# FY.net
KiCad netlist of a schematic drawn in EAGLE
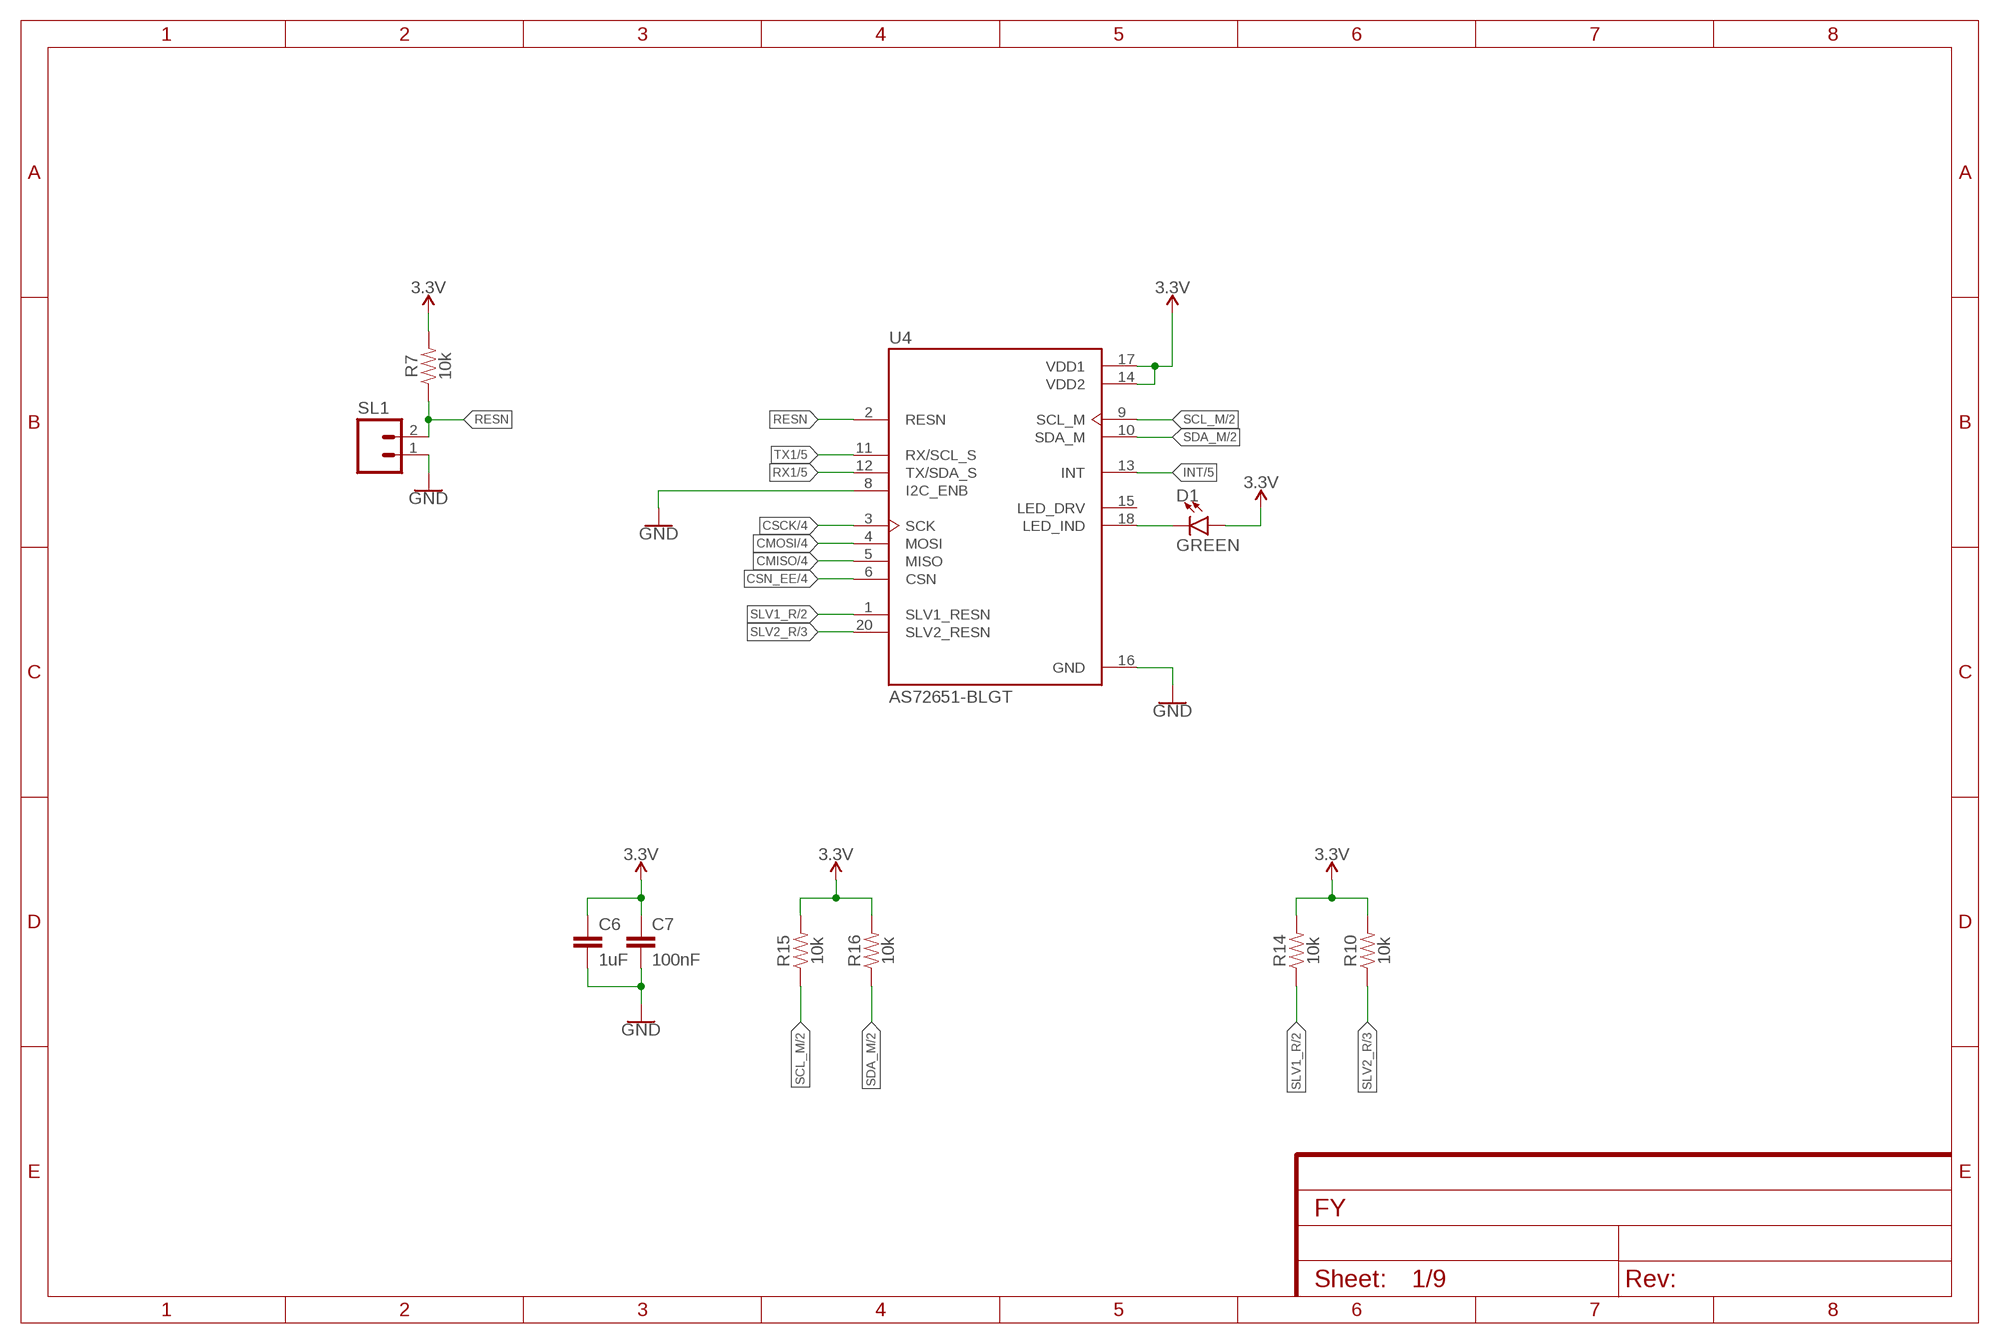
[diagram p0: schematic, sheet 1]
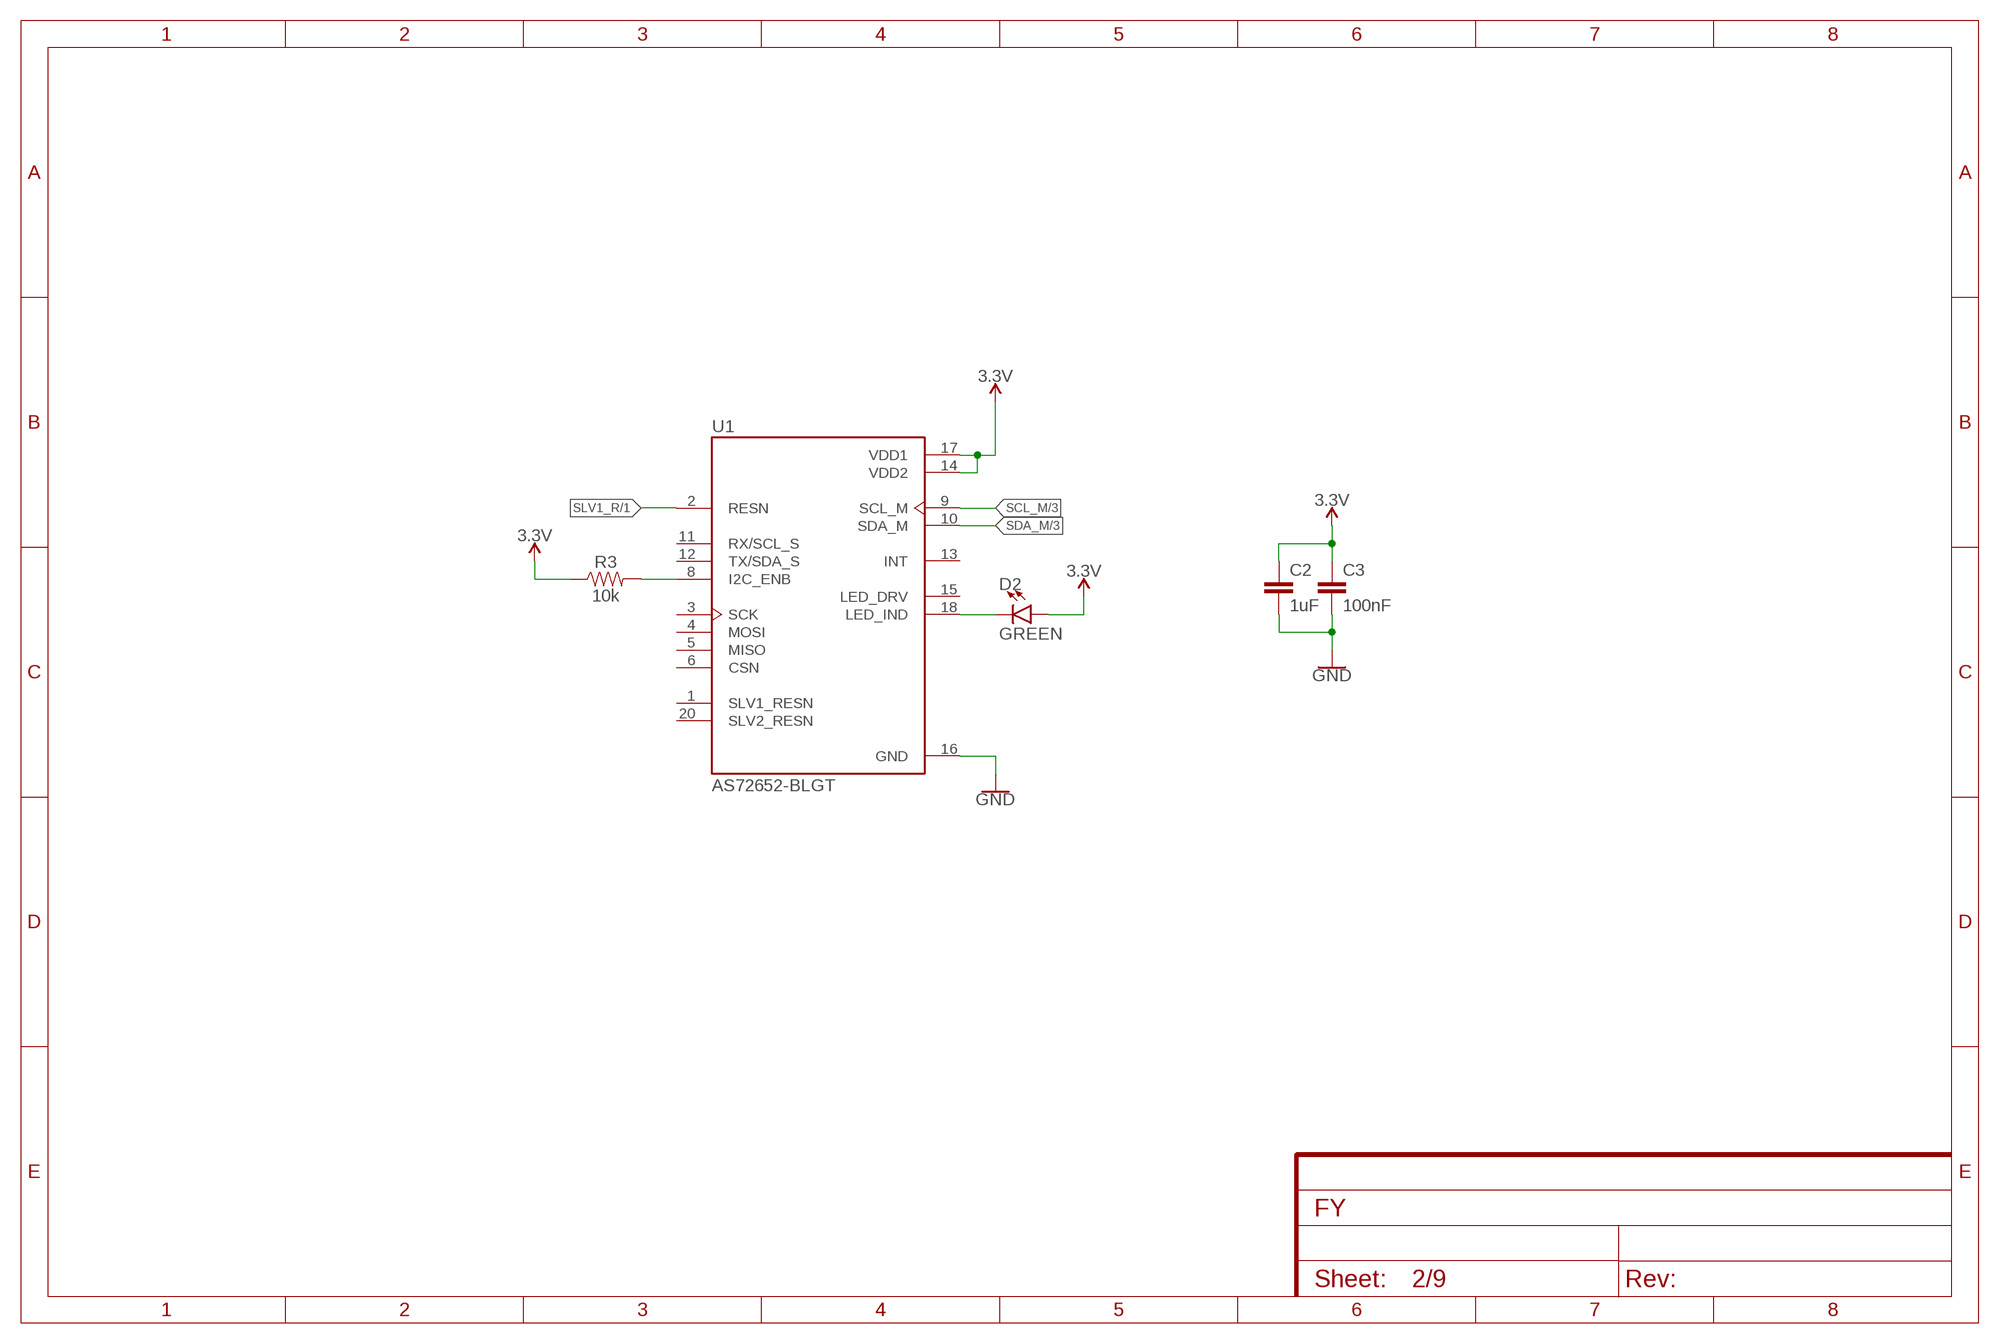
[diagram p1: schematic, sheet 2]
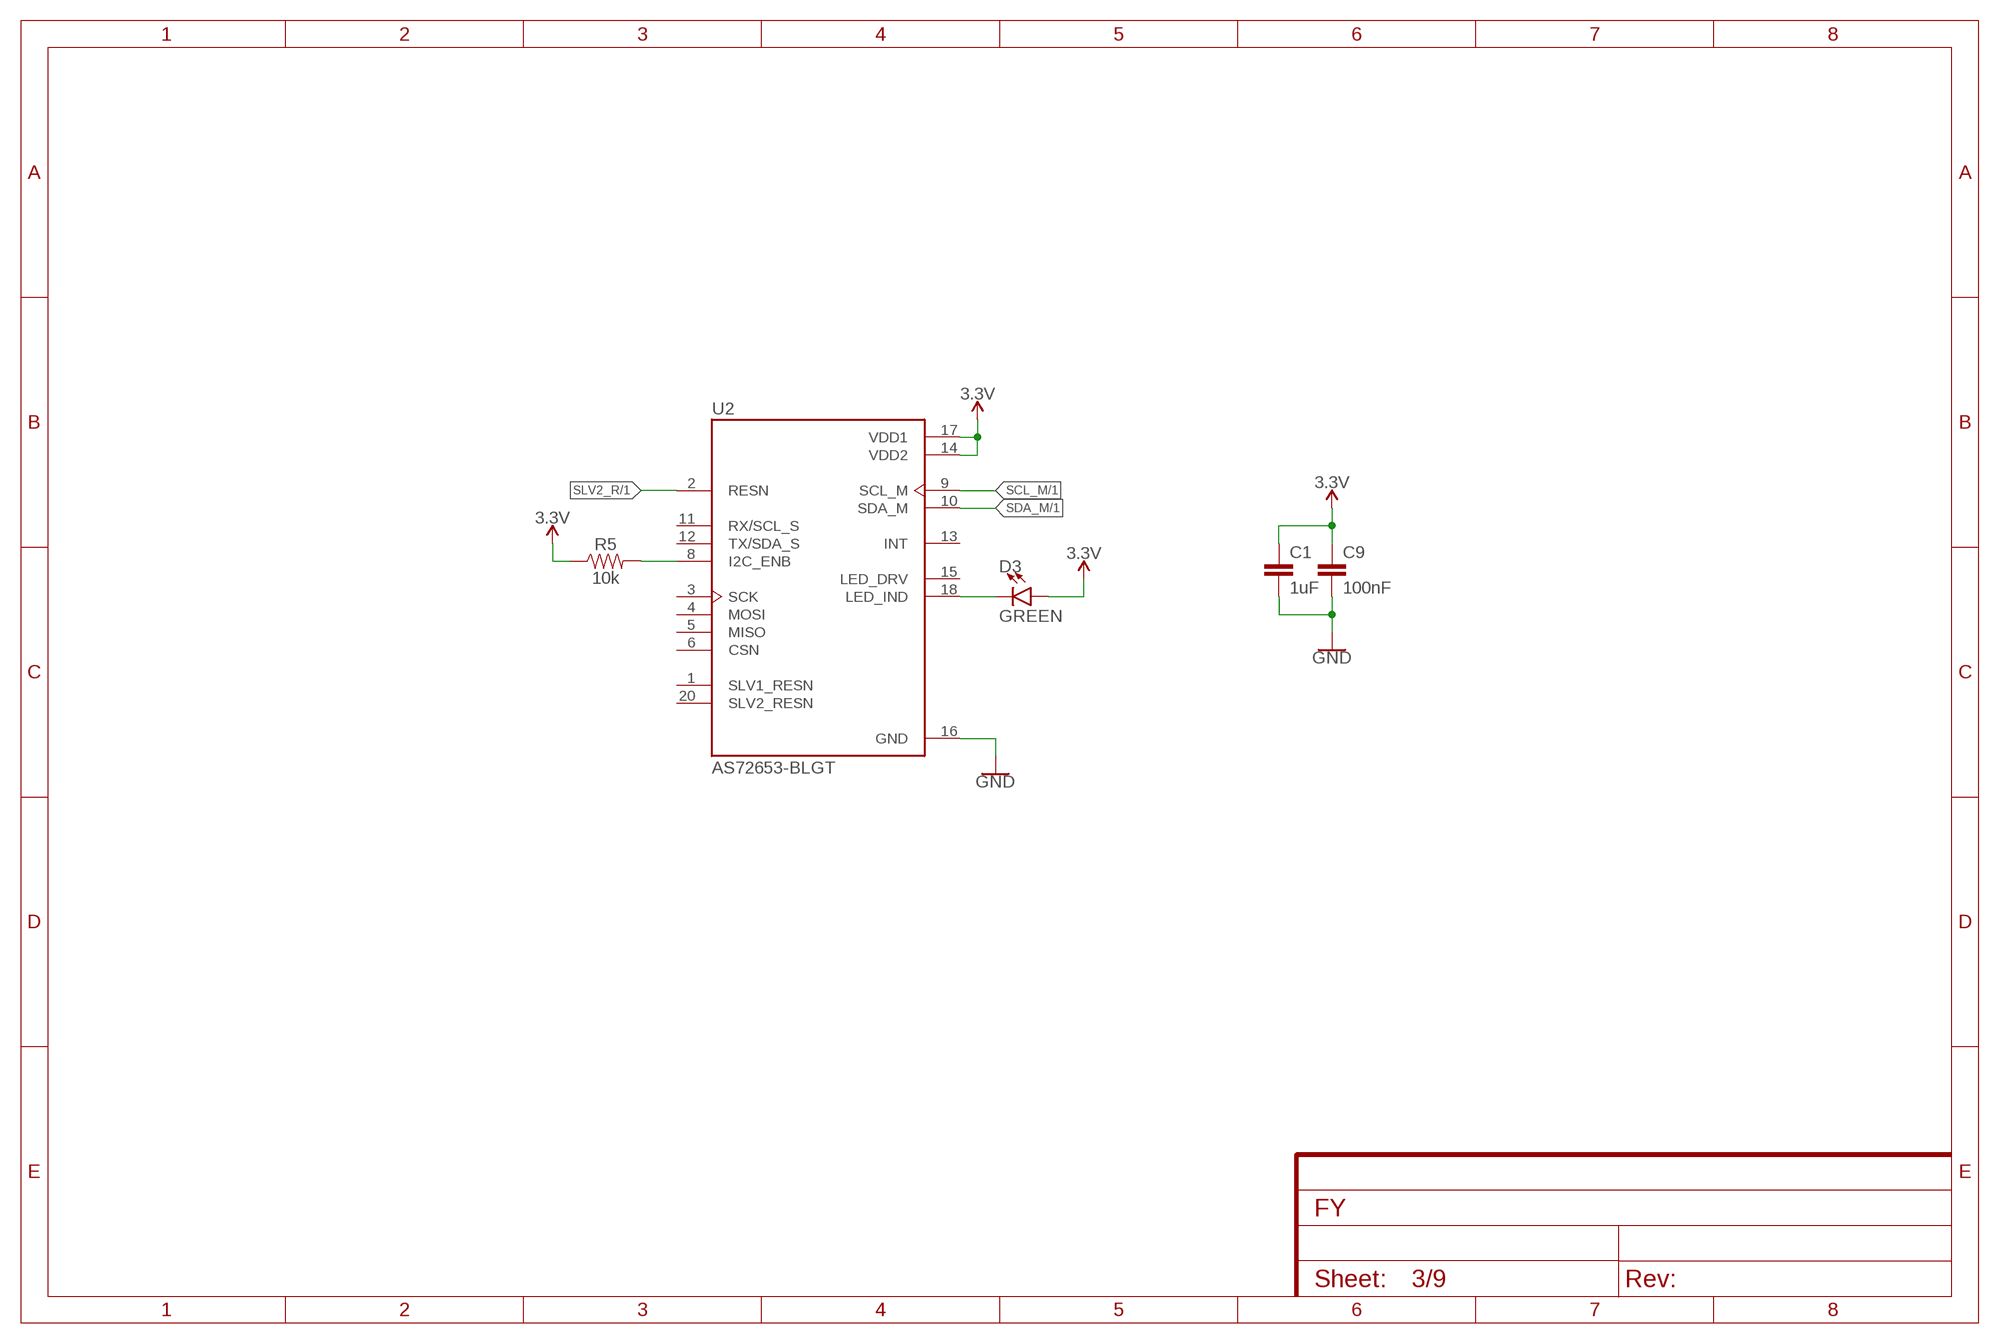
[diagram p2: schematic, sheet 3]
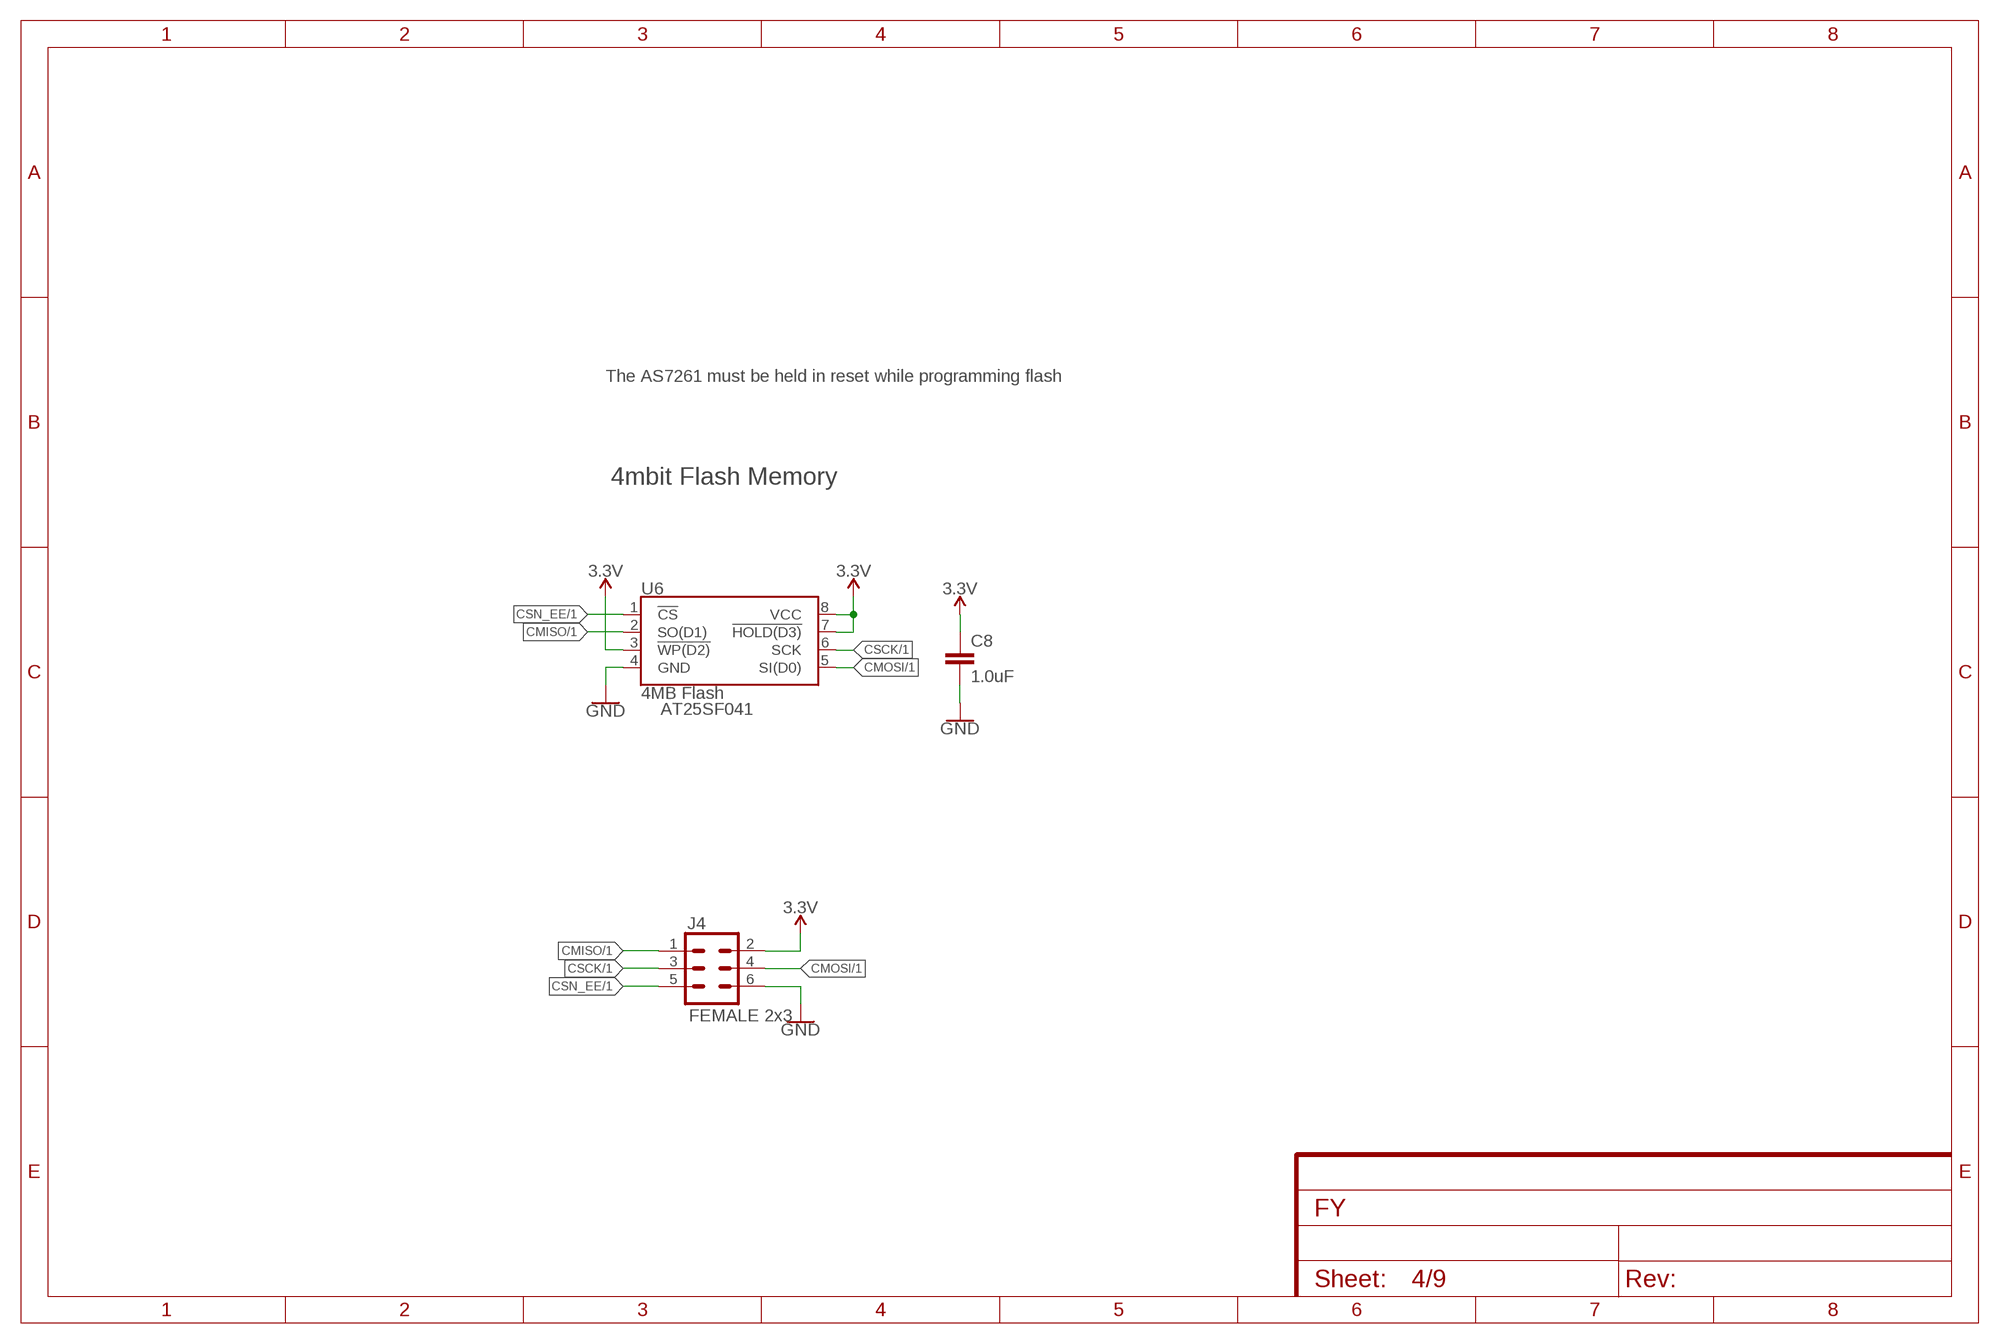
[diagram p3: schematic, sheet 4]
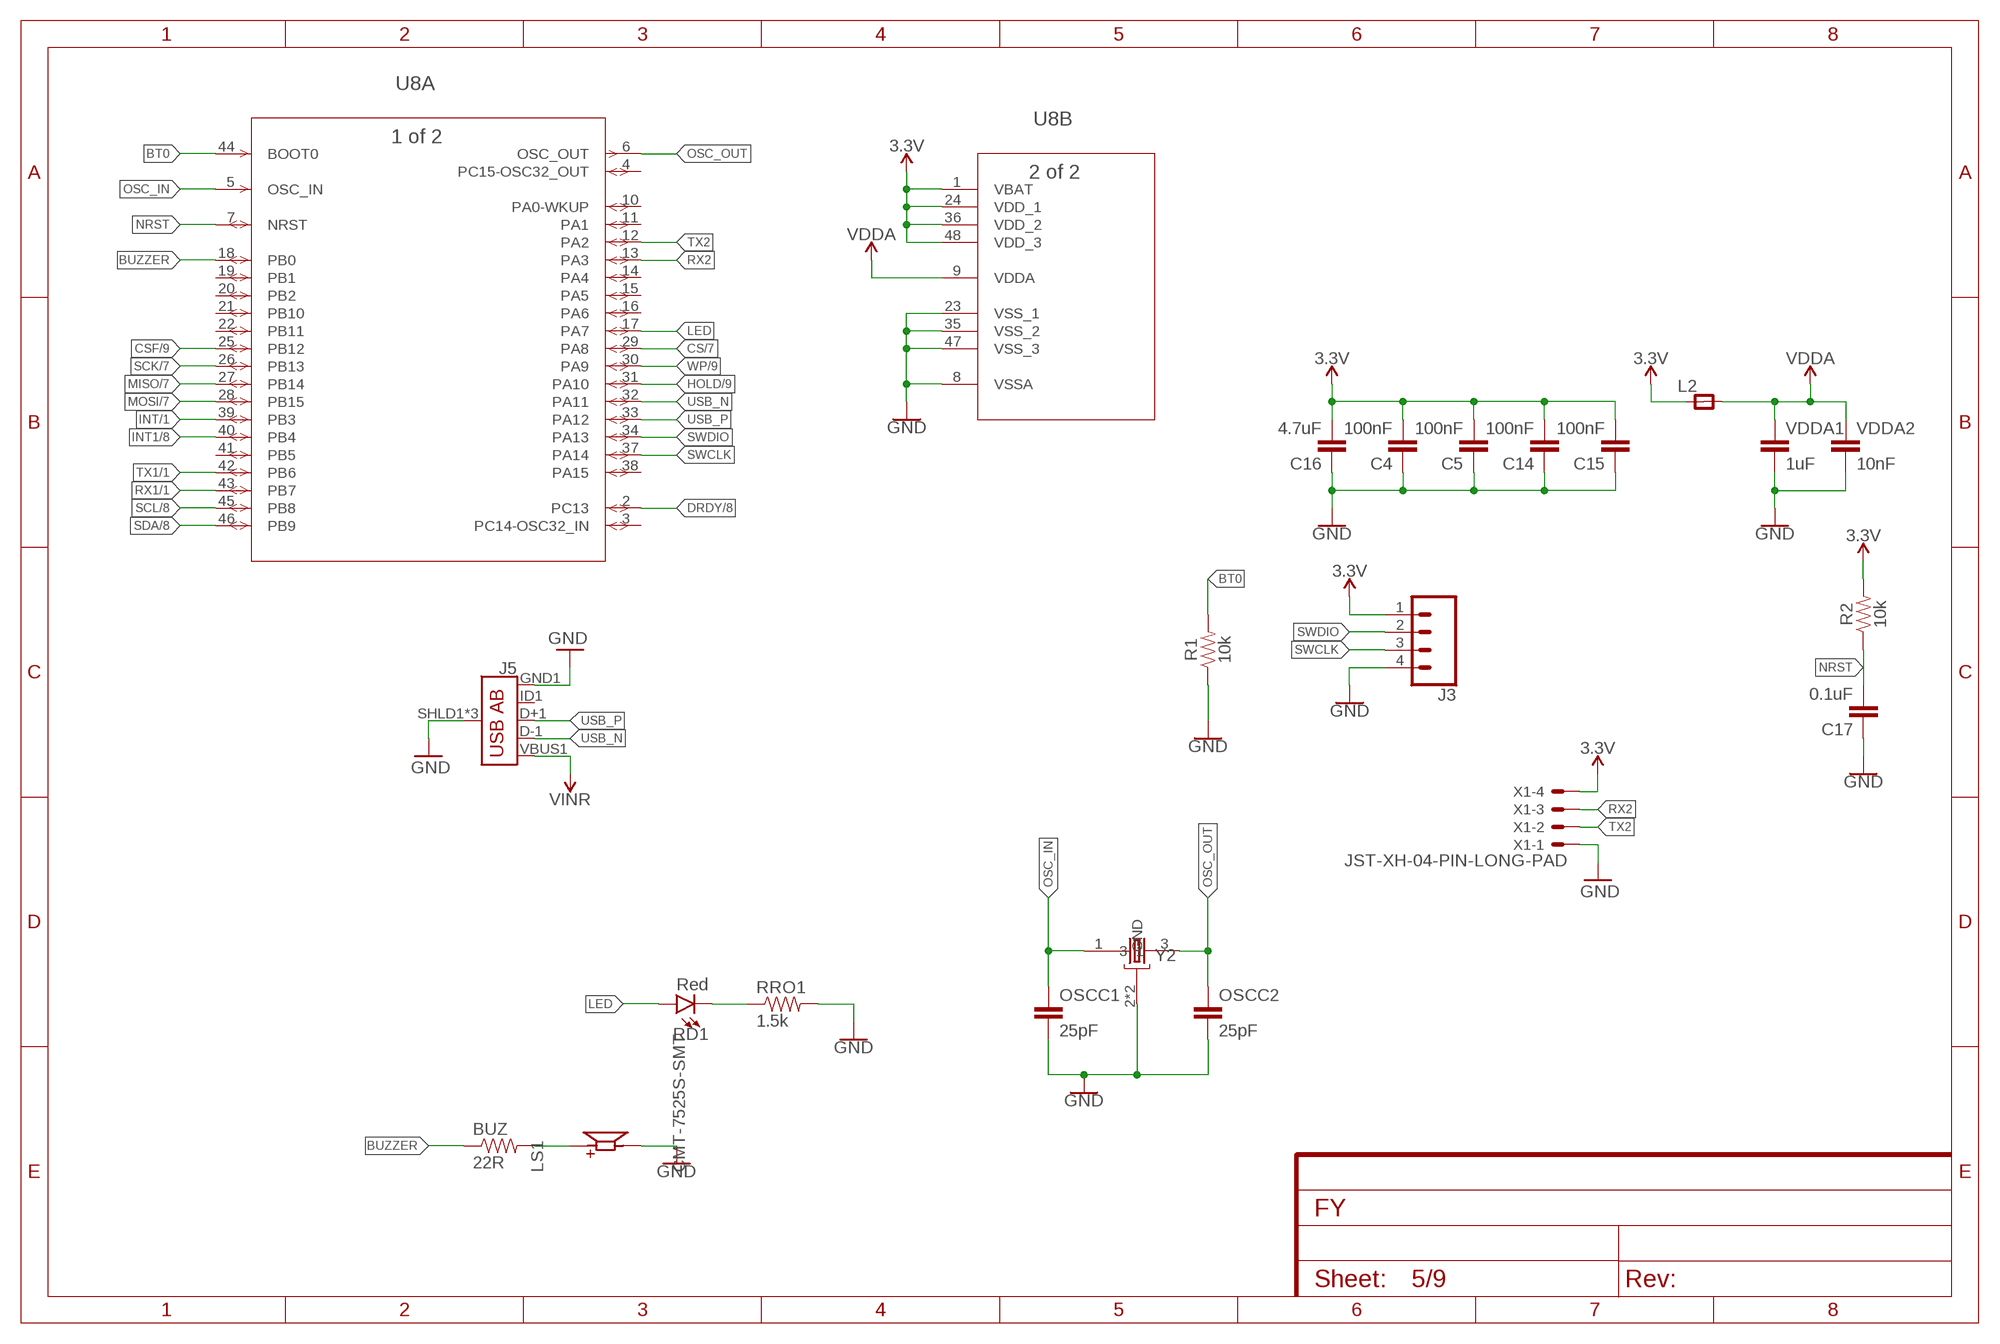
[diagram p4: schematic, sheet 5]
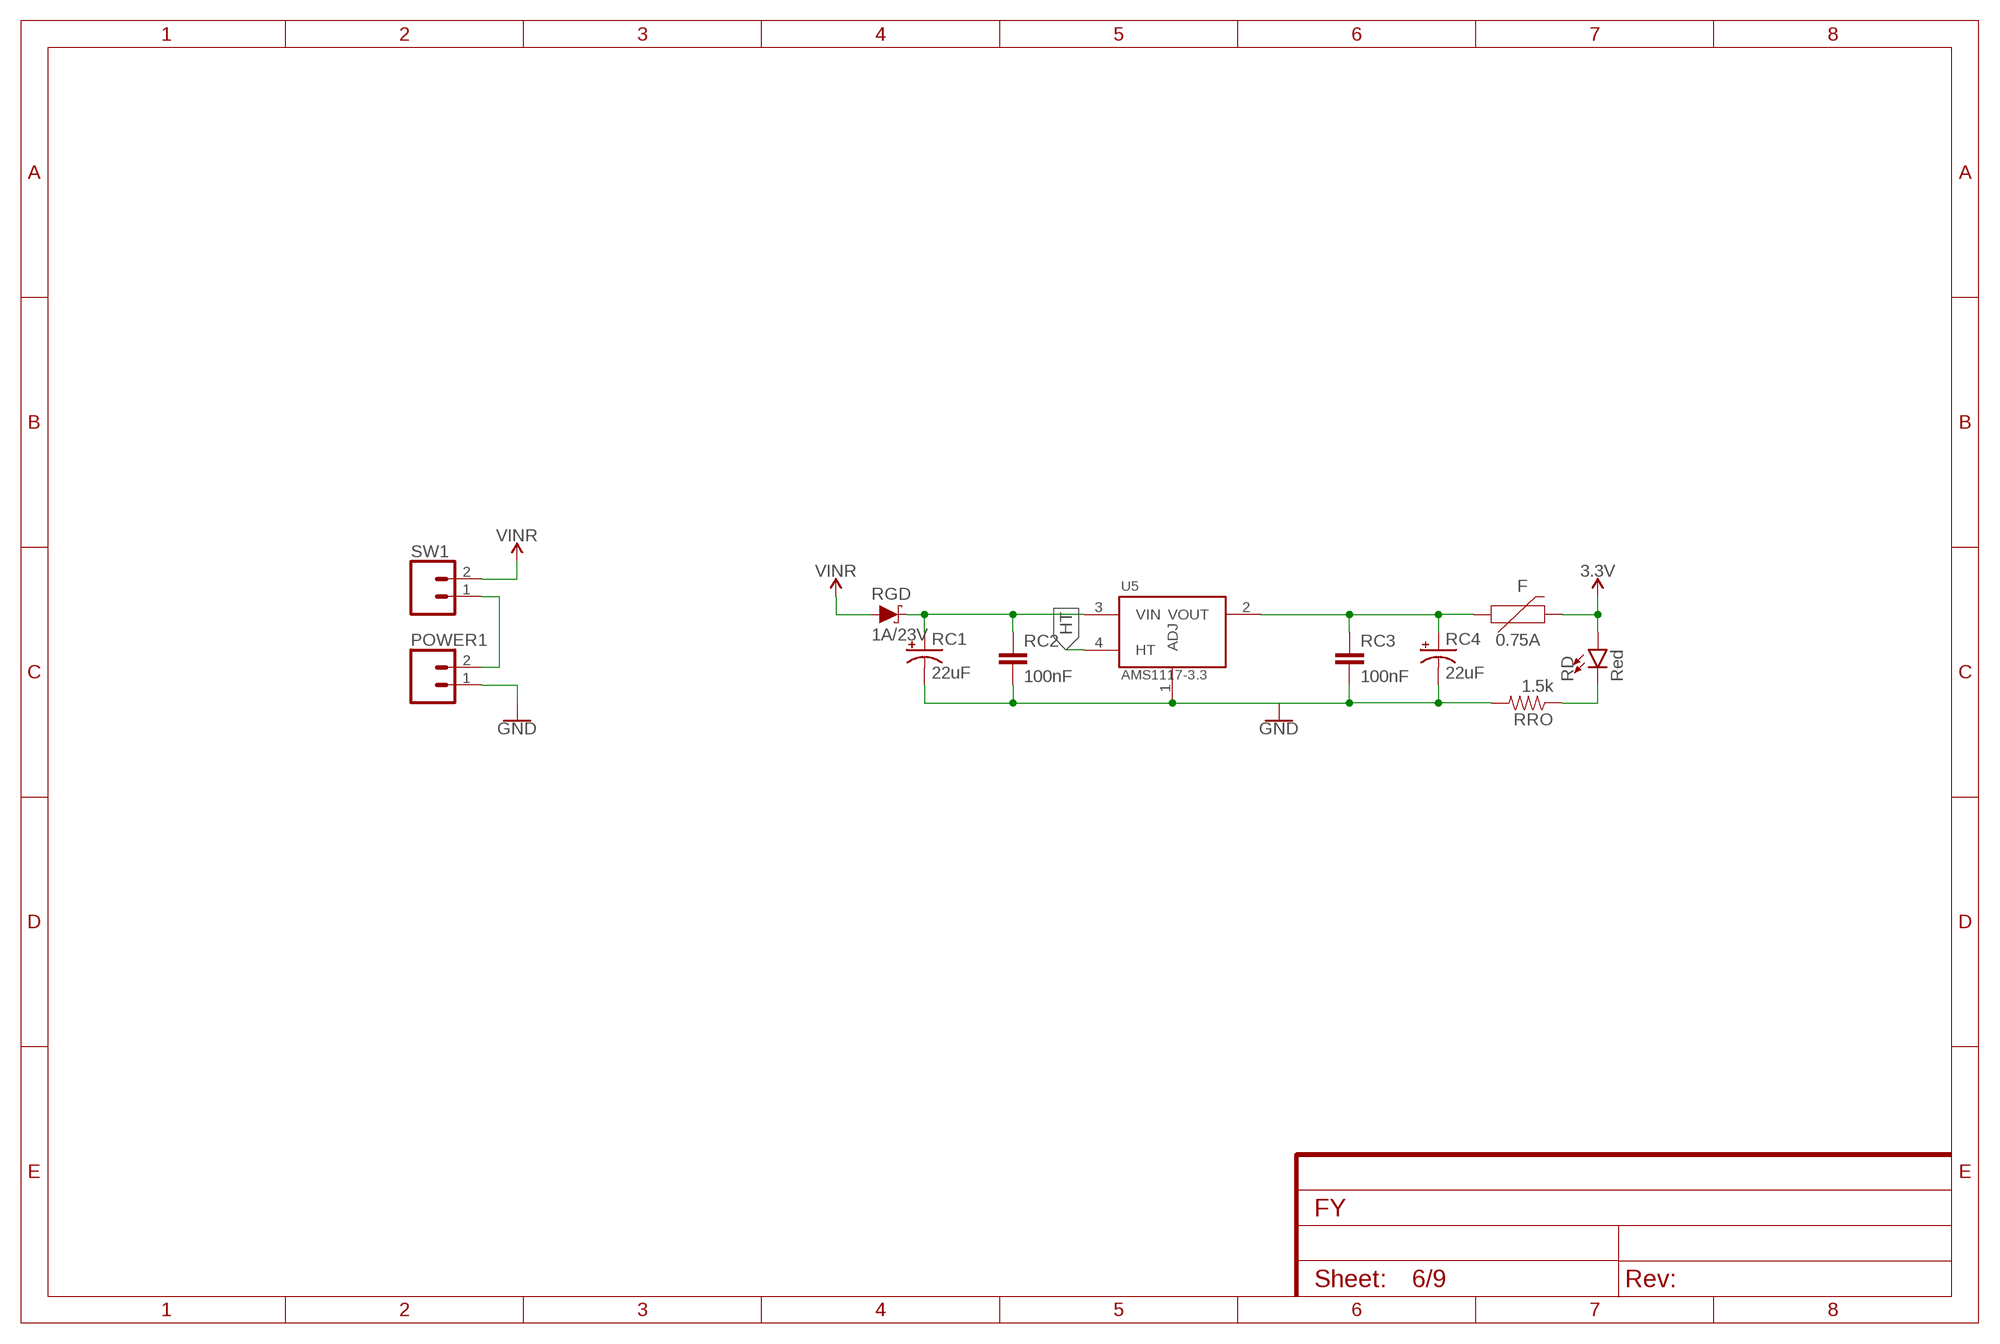
[diagram p5: schematic, sheet 6]
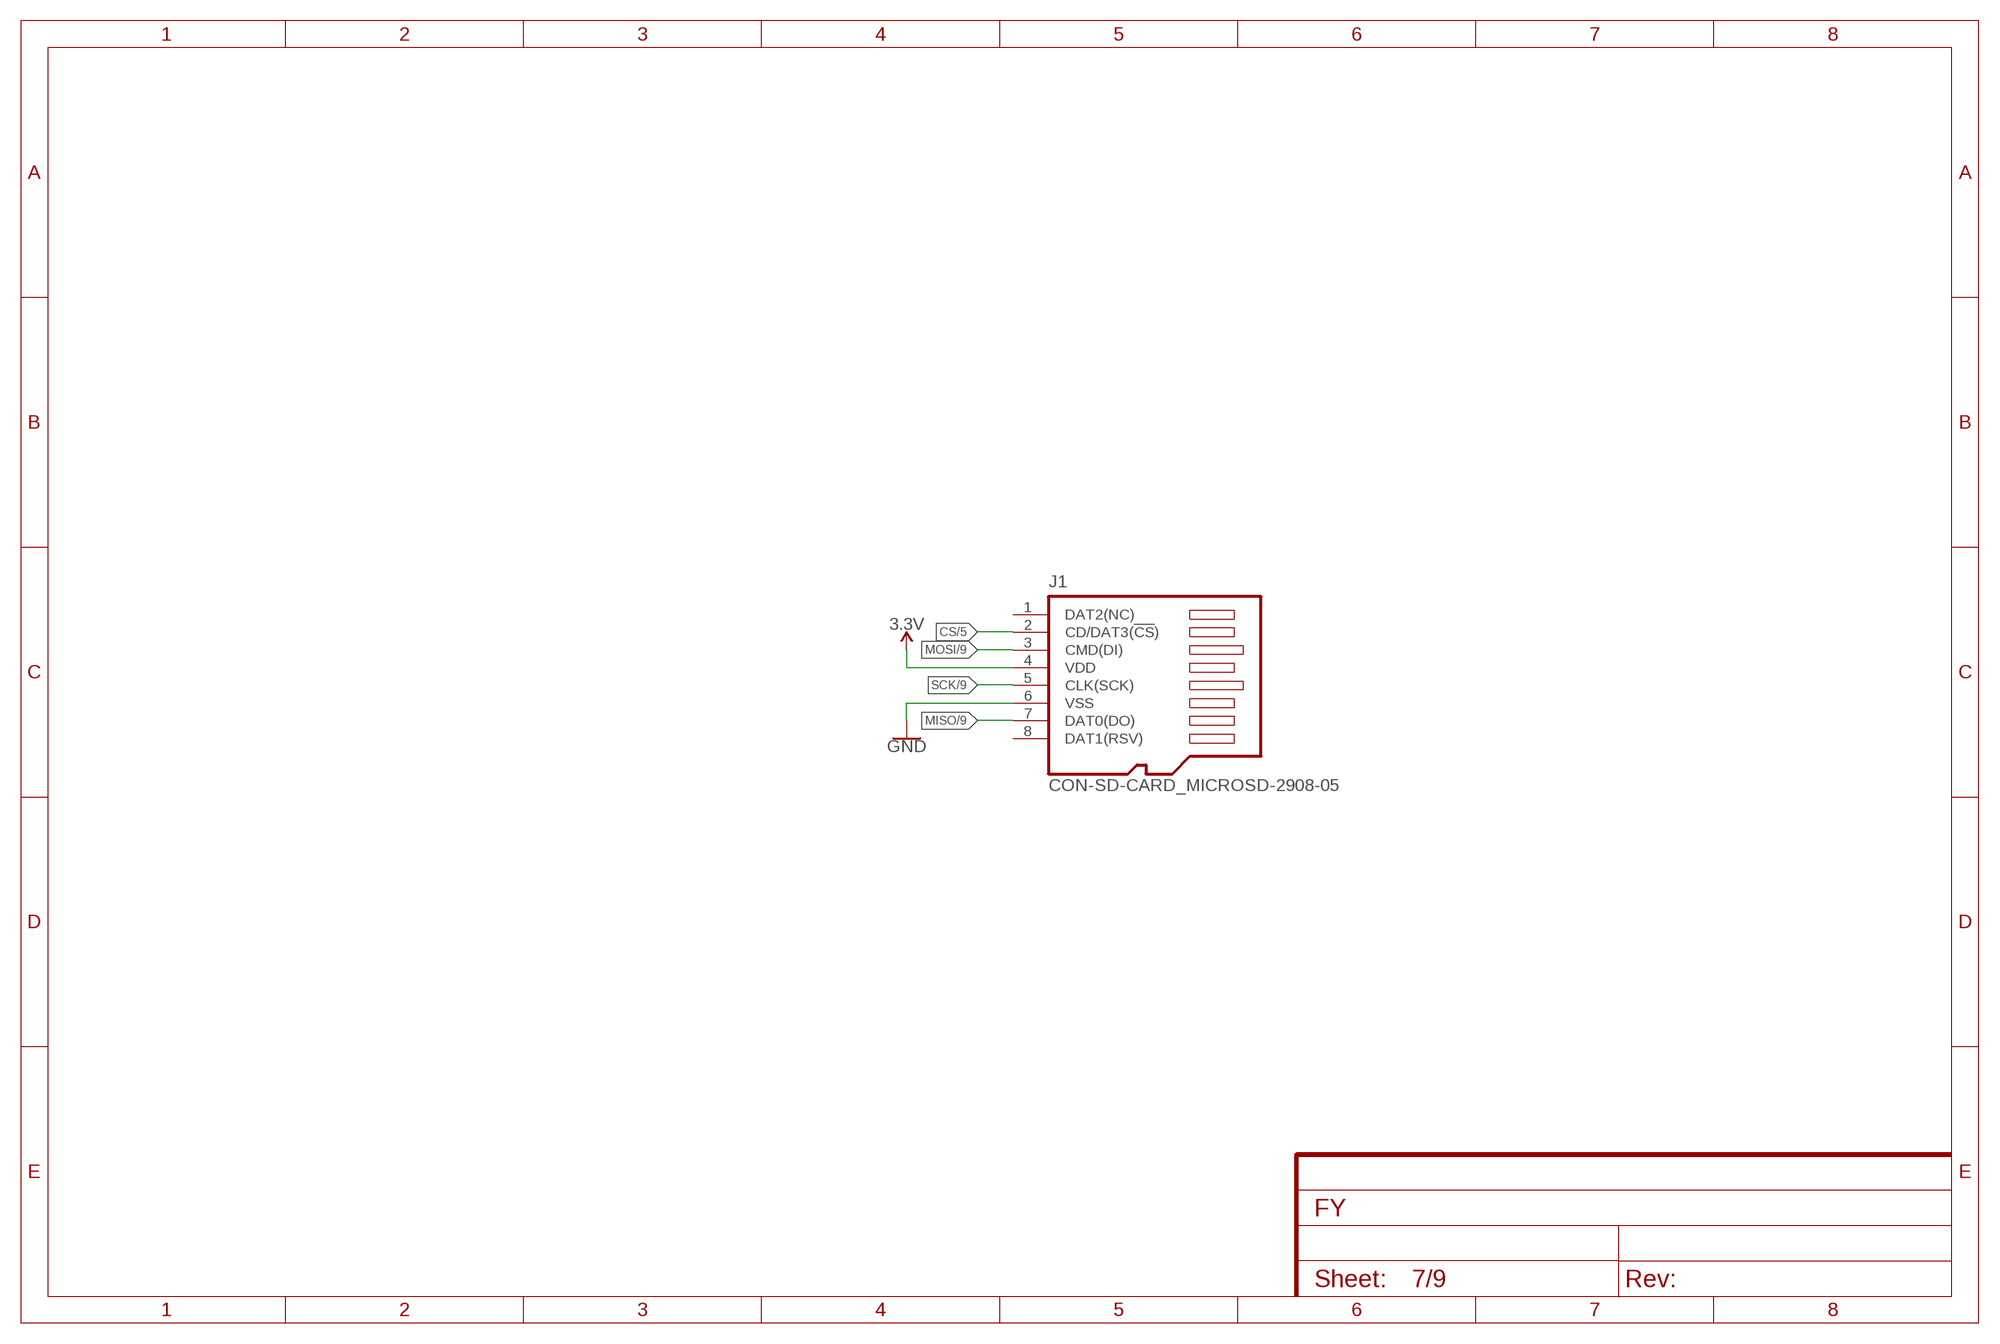
[diagram p6: schematic, sheet 7]
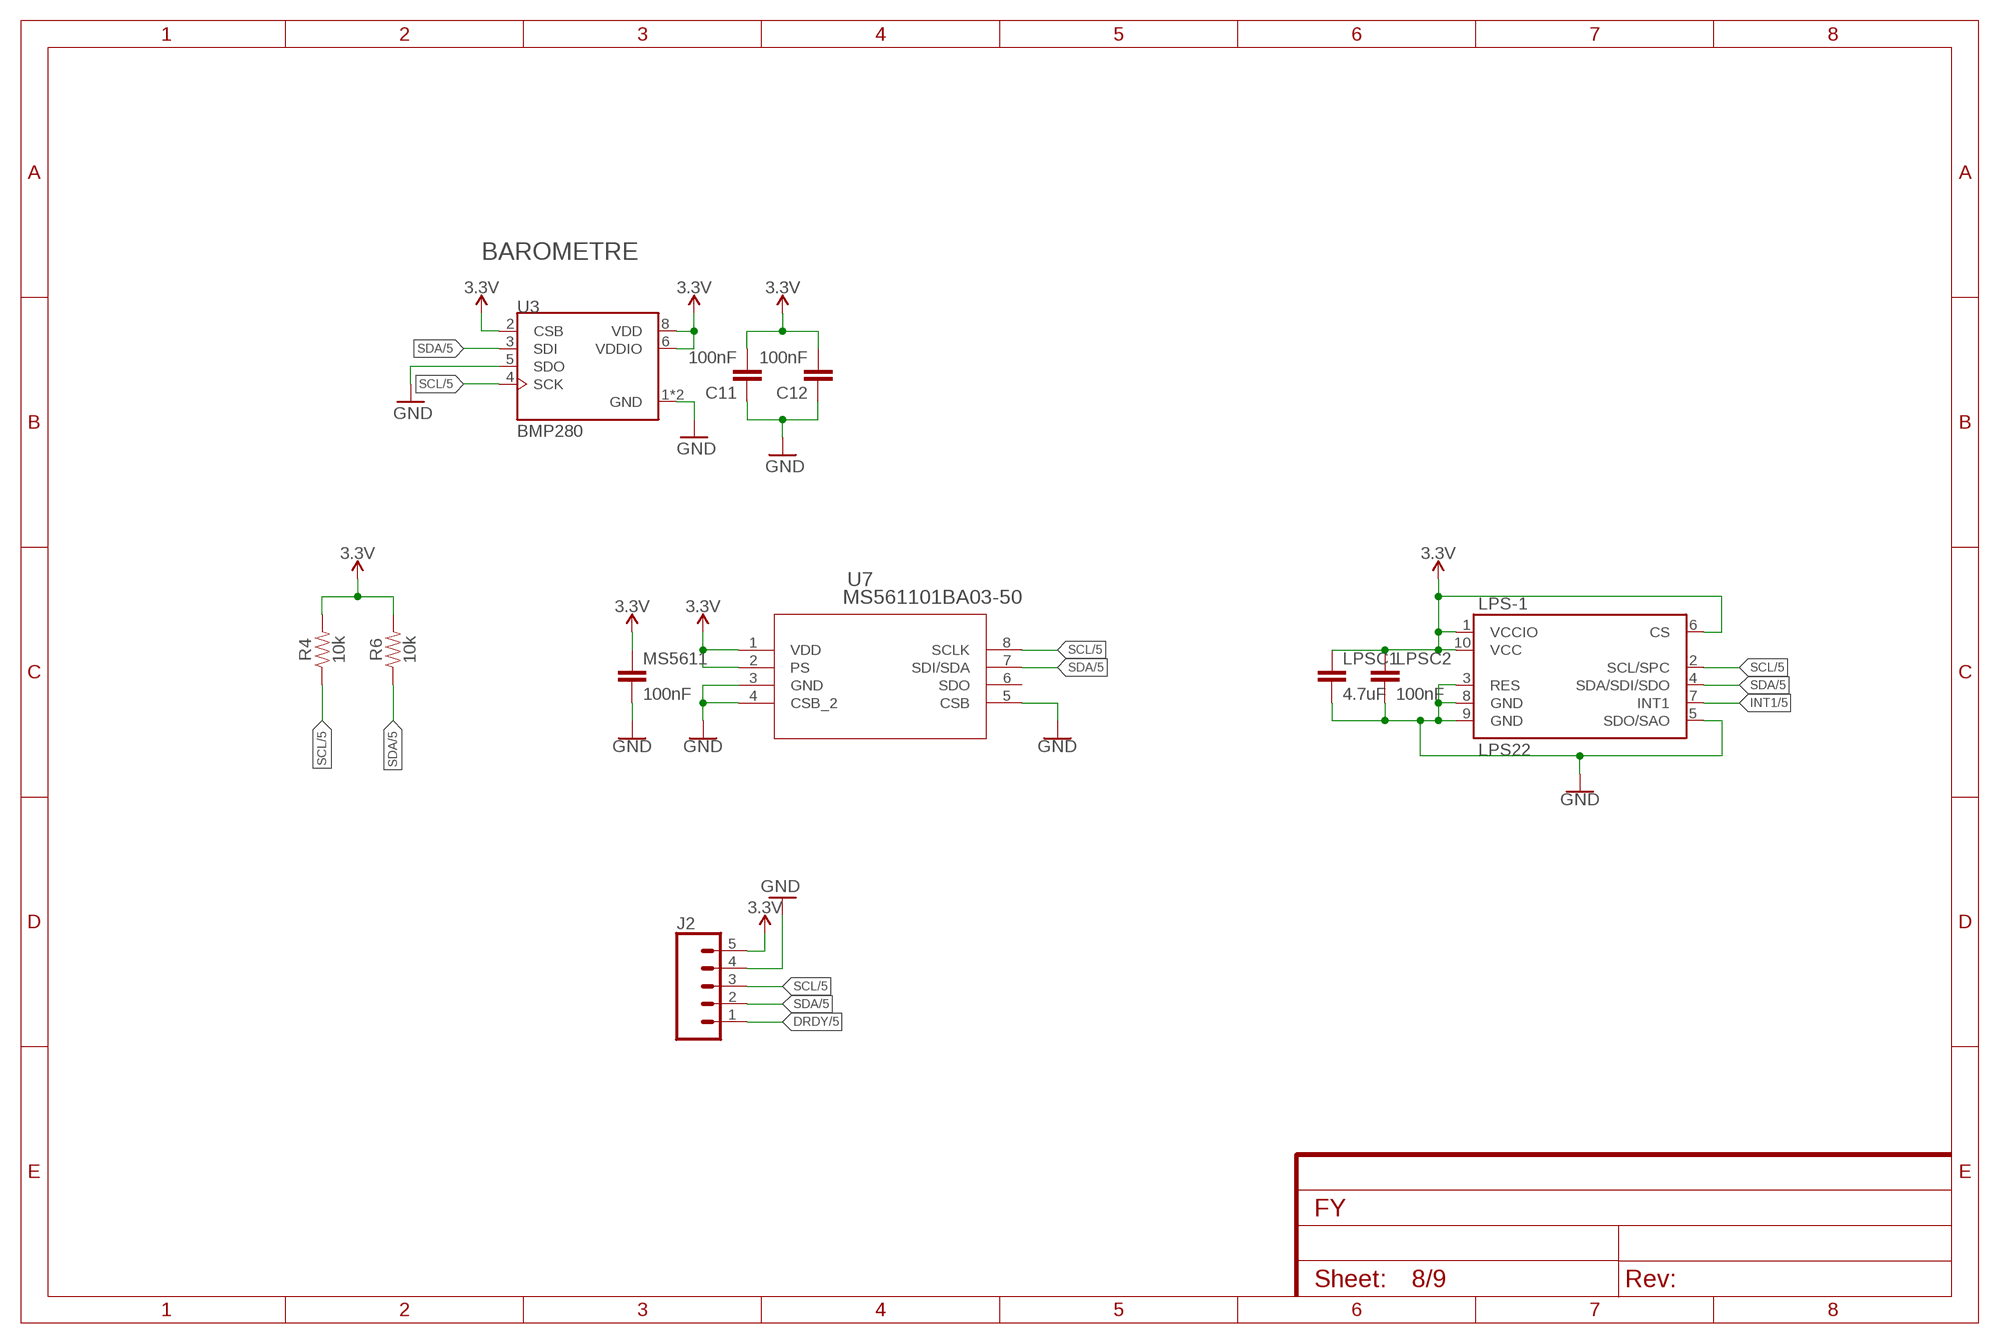
[diagram p7: schematic, sheet 8]
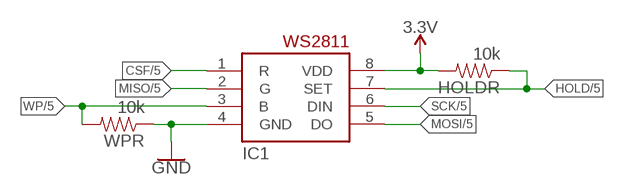
[diagram p8: schematic, sheet 9]

(export (version "E")
  (design (tool "Eeschema 10.0.6"))
  (components
    (comp (ref "F")
      (value "0.75A")
      (footprint "eagle-import:1206")
      (libsource (lib "eagle-import") (part "PPTC_THREE-QUARTER-AMP"))
    )
    (comp (ref "POWER1")
      (value "CONN_023.5MM-NO_SILK")
      (footprint "eagle-import:SCREWTERMINAL-3.5MM-2-NS")
      (libsource (lib "eagle-import") (part "CONN_023.5MM-NO_SILK"))
    )
    (comp (ref "RC1")
      (value "22uF")
      (footprint "eagle-import:EIA3528")
      (libsource (lib "eagle-import") (part "10UF-POLAR-EIA3528-20V-10%(TANT)"))
    )
    (comp (ref "RC2")
      (value "100nF")
      (footprint "eagle-import:0603")
      (libsource (lib "eagle-import") (part "SparkFun-Capacitors_510_0.1UF-0603-25V-(+80/-20%)"))
    )
    (comp (ref "RC3")
      (value "100nF")
      (footprint "eagle-import:0603")
      (libsource (lib "eagle-import") (part "SparkFun-Capacitors_510_0.1UF-0603-25V-(+80/-20%)"))
    )
    (comp (ref "RC4")
      (value "22uF")
      (footprint "eagle-import:EIA3528")
      (libsource (lib "eagle-import") (part "10UF-POLAR-EIA3528-20V-10%(TANT)"))
    )
    (comp (ref "RD")
      (value "Red")
      (footprint "eagle-import:LED-0603")
      (libsource (lib "eagle-import") (part "LED-RED0603-SMART"))
    )
    (comp (ref "RGD")
      (value "1A/23V")
      (footprint "eagle-import:SOD-323")
      (libsource (lib "eagle-import") (part "DIODE-SCHOTTKY-BAT20J"))
    )
    (comp (ref "RRO")
      (value "1.5k")
      (footprint "eagle-import:0603-RES")
      (libsource (lib "eagle-import") (part "2.0KOHM1/10W5%(0603)"))
    )
    (comp (ref "SW1")
      (value "CONN_023.5MM-NO_SILK")
      (footprint "eagle-import:SCREWTERMINAL-3.5MM-2-NS")
      (libsource (lib "eagle-import") (part "CONN_023.5MM-NO_SILK"))
    )
    (comp (ref "U5")
      (value "AMS1117-3.3")
      (footprint "eagle-import:SOT229P700X180-4N")
      (fields (field (name "MF") "Advanced Monolithic Systems"))
      (libsource (lib "eagle-import") (part "AMS1117-3.3"))
    )
    (comp (ref "C8")
      (value "1.0uF")
      (footprint "eagle-import:0603")
      (libsource (lib "eagle-import") (part "1.0UF-0603-16V-10%"))
    )
    (comp (ref "J4")
      (value "FEMALE 2x3")
      (footprint "eagle-import:2X3")
      (libsource (lib "eagle-import") (part "CONN_03X2FEMALE"))
    )
    (comp (ref "U6")
      (value "4MB Flash")
      (footprint "eagle-import:SO08")
      (libsource (lib "eagle-import") (part "AT25SF041"))
    )
    (comp (ref "C11")
      (value "100nF")
      (footprint "eagle-import:0603")
      (libsource (lib "eagle-import") (part "SparkFun-Capacitors_510_1.0UF-0603-16V-10%"))
    )
    (comp (ref "C12")
      (value "100nF")
      (footprint "eagle-import:0603")
      (libsource (lib "eagle-import") (part "SparkFun-Capacitors_510_1.0UF-0603-16V-10%"))
    )
    (comp (ref "J2")
      (value "CONN_05LOCK_LONGPADS")
      (footprint "eagle-import:1X05_LOCK_LONGPADS")
      (libsource (lib "eagle-import") (part "CONN_05LOCK_LONGPADS"))
    )
    (comp (ref "LPS-1")
      (value "LPS22")
      (footprint "eagle-import:LPS22H")
      (fields (field (name "MANUFACTURER") "ST"))
      (libsource (lib "eagle-import") (part "LPS2XH-22"))
    )
    (comp (ref "LPSC1")
      (value "4.7uF")
      (footprint "eagle-import:0603")
      (libsource (lib "eagle-import") (part "SparkFun-Capacitors_510_0.1UF-0603-25V-(+80/-20%)"))
    )
    (comp (ref "LPSC2")
      (value "100nF")
      (footprint "eagle-import:0603")
      (libsource (lib "eagle-import") (part "SparkFun-Capacitors_510_0.1UF-0603-25V-(+80/-20%)"))
    )
    (comp (ref "MS5611")
      (value "100nF")
      (footprint "eagle-import:0603")
      (libsource (lib "eagle-import") (part "SparkFun-Capacitors_510_0.1UF-0603-25V-(+80/-20%)"))
    )
    (comp (ref "R4")
      (value "10k")
      (footprint "eagle-import:0603")
      (libsource (lib "eagle-import") (part "10KOHM-0603-1/10W-1%"))
    )
    (comp (ref "R6")
      (value "10k")
      (footprint "eagle-import:0603")
      (libsource (lib "eagle-import") (part "10KOHM-0603-1/10W-1%"))
    )
    (comp (ref "U3")
      (value "BMP280")
      (footprint "eagle-import:XDCR_BMP280")
      (fields (field (name "MF") "Bosch"))
      (libsource (lib "eagle-import") (part "BMP280"))
    )
    (comp (ref "U7")
      (value "MS561101BA03-50")
      (footprint "eagle-import:SON8_MS5611_TEC")
      (fields (field (name "COPYRIGHT") "Copyright (C) 2016 Accelerated Designs. All rights reserved"))
      (libsource (lib "eagle-import") (part "MS561101BA03-50"))
    )
    (comp (ref "BUZ")
      (value "22R")
      (footprint "eagle-import:0603-RES")
      (libsource (lib "eagle-import") (part "2.0KOHM1/10W5%(0603)"))
    )
    (comp (ref "C4")
      (value "100nF")
      (footprint "eagle-import:0603")
      (libsource (lib "eagle-import") (part "22PF-0603-50V-5%"))
    )
    (comp (ref "C5")
      (value "100nF")
      (footprint "eagle-import:0603")
      (libsource (lib "eagle-import") (part "22PF-0603-50V-5%"))
    )
    (comp (ref "C14")
      (value "100nF")
      (footprint "eagle-import:0603")
      (libsource (lib "eagle-import") (part "22PF-0603-50V-5%"))
    )
    (comp (ref "C15")
      (value "100nF")
      (footprint "eagle-import:0603")
      (libsource (lib "eagle-import") (part "22PF-0603-50V-5%"))
    )
    (comp (ref "C16")
      (value "4.7uF")
      (footprint "eagle-import:0603")
      (libsource (lib "eagle-import") (part "22PF-0603-50V-5%"))
    )
    (comp (ref "C17")
      (value "0.1uF")
      (footprint "eagle-import:0603")
      (libsource (lib "eagle-import") (part "22PF-0603-50V-5%"))
    )
    (comp (ref "J3")
      (value "CONN_04")
      (footprint "eagle-import:1X04")
      (libsource (lib "eagle-import") (part "CONN_04"))
    )
    (comp (ref "J5")
      (value "USB_AB_SMT")
      (footprint "eagle-import:USB-AB-MICRO-SMD")
      (libsource (lib "eagle-import") (part "USB_AB_SMT"))
    )
    (comp (ref "L2")
      (value "RC-MASTER-SMD_FB_0805MP")
      (footprint "eagle-import:RC-MASTER-SMD_L0805MP")
      (libsource (lib "eagle-import") (part "RC-MASTER-SMD_FB_0805MP"))
    )
    (comp (ref "LS1")
      (value "CMT-7525S-SMT")
      (footprint "eagle-import:CUI_CMT-7525S-SMT")
      (fields (field (name "MF") "CUI Devices") (field (name "MP") "CMT-7525S-SMT-TR"))
      (libsource (lib "eagle-import") (part "CMT-7525S-SMT"))
    )
    (comp (ref "OSCC1")
      (value "25pF")
      (footprint "eagle-import:0603")
      (libsource (lib "eagle-import") (part "SparkFun-Capacitors_510_0.1UF-0603-25V-(+80/-20%)"))
    )
    (comp (ref "OSCC2")
      (value "25pF")
      (footprint "eagle-import:0603")
      (libsource (lib "eagle-import") (part "SparkFun-Capacitors_510_0.1UF-0603-25V-(+80/-20%)"))
    )
    (comp (ref "R1")
      (value "10k")
      (footprint "eagle-import:0603")
      (libsource (lib "eagle-import") (part "0.05OHM-0603-1/5W-1%"))
    )
    (comp (ref "R2")
      (value "10k")
      (footprint "eagle-import:0603")
      (libsource (lib "eagle-import") (part "0.05OHM-0603-1/5W-1%"))
    )
    (comp (ref "RD1")
      (value "Red")
      (footprint "eagle-import:LED-0603")
      (libsource (lib "eagle-import") (part "LED-RED0603-SMART"))
    )
    (comp (ref "RRO1")
      (value "1.5k")
      (footprint "eagle-import:0603-RES")
      (libsource (lib "eagle-import") (part "2.0KOHM1/10W5%(0603)"))
    )
    (comp (ref "U8")
      (value "STM32F103C8T6")
      (footprint "eagle-import:LQFP48-7X7MM")
      (fields (field (name "COPYRIGHT") "Copyright (C) 2018 Accelerated Designs. All rights reserved"))
      (libsource (lib "eagle-import") (part "STM32F103C8T6"))
    )
    (comp (ref "VDDA1")
      (value "1uF")
      (footprint "eagle-import:0603")
      (libsource (lib "eagle-import") (part "SparkFun-Capacitors_510_0.1UF-0603-25V-(+80/-20%)"))
    )
    (comp (ref "VDDA2")
      (value "10nF")
      (footprint "eagle-import:0603")
      (libsource (lib "eagle-import") (part "SparkFun-Capacitors_510_0.1UF-0603-25V-(+80/-20%)"))
    )
    (comp (ref "X1")
      (value "JST-XH-04-PIN-LONG-PAD")
      (footprint "eagle-import:JST-XH-04-PACKAGE-LONG-PAD")
      (libsource (lib "eagle-import") (part "JST-XH-04-PIN-LONG-PAD"))
    )
    (comp (ref "Y2")
      (value "ABM2B-8.000MHZ-10-1-U-T")
      (footprint "eagle-import:OSCCC500X320X110-4N")
      (fields (field (name "MF") "Abracon") (field (name "MP") "ABM3B-26.000MHZ-10-1-U-T"))
      (libsource (lib "eagle-import") (part "ABM3B-26.000MHZ-10-1-U-T"))
    )
    (comp (ref "J1")
      (value "CON-SD-CARD_MICROSD-2908-05")
      (footprint "eagle-import:CON-SD-CARD_2908-05")
      (libsource (lib "eagle-import") (part "CON-SD-CARD_MICROSD-2908-05"))
    )
    (comp (ref "C1")
      (value "1uF")
      (footprint "eagle-import:0603")
      (libsource (lib "eagle-import") (part "10UF-0603-6.3V-20%"))
    )
    (comp (ref "C9")
      (value "100nF")
      (footprint "eagle-import:0603")
      (libsource (lib "eagle-import") (part "0.1UF-0603-25V-(+80/-20%)"))
    )
    (comp (ref "D3")
      (value "GREEN")
      (footprint "eagle-import:LED-0603")
      (libsource (lib "eagle-import") (part "LED-GREEN0603"))
    )
    (comp (ref "R5")
      (value "10k")
      (footprint "eagle-import:0603")
      (libsource (lib "eagle-import") (part "0.05OHM-0603-1/5W-1%"))
    )
    (comp (ref "U2")
      (value "AS72653-BLGT")
      (footprint "eagle-import:PQFN65P470X450X270-20N")
      (fields (field (name "MF") "ams") (field (name "MP") "AS72651-BLGT"))
      (libsource (lib "eagle-import") (part "AS72651-BLGT"))
    )
    (comp (ref "C2")
      (value "1uF")
      (footprint "eagle-import:0603")
      (libsource (lib "eagle-import") (part "10UF-0603-6.3V-20%"))
    )
    (comp (ref "C3")
      (value "100nF")
      (footprint "eagle-import:0603")
      (libsource (lib "eagle-import") (part "0.1UF-0603-25V-(+80/-20%)"))
    )
    (comp (ref "D2")
      (value "GREEN")
      (footprint "eagle-import:LED-0603")
      (libsource (lib "eagle-import") (part "LED-GREEN0603"))
    )
    (comp (ref "R3")
      (value "10k")
      (footprint "eagle-import:0603")
      (libsource (lib "eagle-import") (part "0.05OHM-0603-1/5W-1%"))
    )
    (comp (ref "U1")
      (value "AS72652-BLGT")
      (footprint "eagle-import:PQFN65P470X450X270-20N")
      (fields (field (name "MF") "ams") (field (name "MP") "AS72651-BLGT"))
      (libsource (lib "eagle-import") (part "AS72651-BLGT"))
    )
    (comp (ref "C6")
      (value "1uF")
      (footprint "eagle-import:0603")
      (libsource (lib "eagle-import") (part "10UF-0603-6.3V-20%"))
    )
    (comp (ref "C7")
      (value "100nF")
      (footprint "eagle-import:0603")
      (libsource (lib "eagle-import") (part "0.1UF-0603-25V-(+80/-20%)"))
    )
    (comp (ref "D1")
      (value "GREEN")
      (footprint "eagle-import:LED-0603")
      (libsource (lib "eagle-import") (part "LED-GREEN0603"))
    )
    (comp (ref "R7")
      (value "10k")
      (footprint "eagle-import:0603")
      (libsource (lib "eagle-import") (part "10KOHM-0603-1/10W-1%"))
    )
    (comp (ref "R10")
      (value "10k")
      (footprint "eagle-import:0603")
      (libsource (lib "eagle-import") (part "10KOHM-0603-1/10W-1%"))
    )
    (comp (ref "R14")
      (value "10k")
      (footprint "eagle-import:0603")
      (libsource (lib "eagle-import") (part "10KOHM-0603-1/10W-1%"))
    )
    (comp (ref "R15")
      (value "10k")
      (footprint "eagle-import:0603")
      (libsource (lib "eagle-import") (part "10KOHM-0603-1/10W-1%"))
    )
    (comp (ref "R16")
      (value "10k")
      (footprint "eagle-import:0603")
      (libsource (lib "eagle-import") (part "10KOHM-0603-1/10W-1%"))
    )
    (comp (ref "SL1")
      (value "M02")
      (footprint "eagle-import:02P")
      (libsource (lib "eagle-import") (part "M02"))
    )
    (comp (ref "U4")
      (value "AS72651-BLGT")
      (footprint "eagle-import:PQFN65P470X450X270-20N")
      (fields (field (name "MF") "ams"))
      (libsource (lib "eagle-import") (part "AS72651-BLGT"))
    )
    (comp (ref "HOLDR")
      (value "10k")
      (footprint "eagle-import:0603-RES")
      (libsource (lib "eagle-import") (part "2.0KOHM1/10W5%(0603)"))
    )
    (comp (ref "IC1")
      (value "EN25F40-100GCP-TR")
      (footprint "eagle-import:SO08-SKINNYPADS")
      (libsource (lib "eagle-import") (part "WS2811-SOP8"))
    )
    (comp (ref "WPR")
      (value "10k")
      (footprint "eagle-import:0603-RES")
      (libsource (lib "eagle-import") (part "2.0KOHM1/10W5%(0603)"))
    )
  )
  (nets
    (net (code "1") (name "3.3V") (class "Default")
      (node (ref "C1") (pin "1") (pinfunction "1_1") (pintype "passive"))
      (node (ref "C11") (pin "2") (pinfunction "2_2") (pintype "passive"))
      (node (ref "C12") (pin "2") (pinfunction "2_2") (pintype "passive"))
      (node (ref "C14") (pin "2") (pinfunction "2_2") (pintype "passive"))
      (node (ref "C15") (pin "2") (pinfunction "2_2") (pintype "passive"))
      (node (ref "C16") (pin "2") (pinfunction "2_2") (pintype "passive"))
      (node (ref "C2") (pin "1") (pinfunction "1_1") (pintype "passive"))
      (node (ref "C3") (pin "1") (pinfunction "1_1") (pintype "passive"))
      (node (ref "C4") (pin "2") (pinfunction "2_2") (pintype "passive"))
      (node (ref "C5") (pin "2") (pinfunction "2_2") (pintype "passive"))
      (node (ref "C6") (pin "1") (pinfunction "1_1") (pintype "passive"))
      (node (ref "C7") (pin "1") (pinfunction "1_1") (pintype "passive"))
      (node (ref "C8") (pin "1") (pinfunction "1_1") (pintype "passive"))
      (node (ref "C9") (pin "1") (pinfunction "1_1") (pintype "passive"))
      (node (ref "D1") (pin "A") (pinfunction "A_A") (pintype "passive"))
      (node (ref "D2") (pin "A") (pinfunction "A_A") (pintype "passive"))
      (node (ref "D3") (pin "A") (pinfunction "A_A") (pintype "passive"))
      (node (ref "F") (pin "2") (pinfunction "2_2") (pintype "bidirectional"))
      (node (ref "HOLDR") (pin "2") (pinfunction "2_2") (pintype "passive"))
      (node (ref "IC1") (pin "8") (pinfunction "VDD_8") (pintype "power_in"))
      (node (ref "J1") (pin "4") (pinfunction "VDD_4") (pintype "bidirectional"))
      (node (ref "J2") (pin "5") (pinfunction "5_5") (pintype "passive"))
      (node (ref "J3") (pin "1") (pinfunction "1_1") (pintype "passive"))
      (node (ref "J4") (pin "2") (pinfunction "2_2") (pintype "bidirectional"))
      (node (ref "L2") (pin "1") (pinfunction "1_1") (pintype "passive"))
      (node (ref "LPS-1") (pin "1") (pinfunction "VCCIO_1") (pintype "bidirectional"))
      (node (ref "LPS-1") (pin "10") (pinfunction "VCC_10") (pintype "bidirectional"))
      (node (ref "LPS-1") (pin "6") (pinfunction "CS_6") (pintype "bidirectional"))
      (node (ref "LPSC1") (pin "1") (pinfunction "1_1") (pintype "passive"))
      (node (ref "LPSC2") (pin "1") (pinfunction "1_1") (pintype "passive"))
      (node (ref "MS5611") (pin "1") (pinfunction "1_1") (pintype "passive"))
      (node (ref "R10") (pin "2") (pinfunction "2_2") (pintype "passive"))
      (node (ref "R14") (pin "2") (pinfunction "2_2") (pintype "passive"))
      (node (ref "R15") (pin "2") (pinfunction "2_2") (pintype "passive"))
      (node (ref "R16") (pin "2") (pinfunction "2_2") (pintype "passive"))
      (node (ref "R2") (pin "2") (pinfunction "2_2") (pintype "passive"))
      (node (ref "R3") (pin "1") (pinfunction "1_1") (pintype "passive"))
      (node (ref "R4") (pin "2") (pinfunction "2_2") (pintype "passive"))
      (node (ref "R5") (pin "1") (pinfunction "1_1") (pintype "passive"))
      (node (ref "R6") (pin "2") (pinfunction "2_2") (pintype "passive"))
      (node (ref "R7") (pin "2") (pinfunction "2_2") (pintype "passive"))
      (node (ref "RD") (pin "A") (pinfunction "A_A") (pintype "passive"))
      (node (ref "U1") (pin "14") (pinfunction "VDD2_14") (pintype "power_in"))
      (node (ref "U1") (pin "17") (pinfunction "VDD1_17") (pintype "power_in"))
      (node (ref "U2") (pin "14") (pinfunction "VDD2_14") (pintype "power_in"))
      (node (ref "U2") (pin "17") (pinfunction "VDD1_17") (pintype "power_in"))
      (node (ref "U3") (pin "2") (pinfunction "CSB_2") (pintype "input"))
      (node (ref "U3") (pin "6") (pinfunction "VDDIO_6") (pintype "power_in"))
      (node (ref "U3") (pin "8") (pinfunction "VDD_8") (pintype "power_in"))
      (node (ref "U4") (pin "14") (pinfunction "VDD2_14") (pintype "power_in"))
      (node (ref "U4") (pin "17") (pinfunction "VDD1_17") (pintype "power_in"))
      (node (ref "U6") (pin "3") (pinfunction "~{WP(D2})_3") (pintype "bidirectional"))
      (node (ref "U6") (pin "7") (pinfunction "~{HOLD(D3})_7") (pintype "bidirectional"))
      (node (ref "U6") (pin "8") (pinfunction "VCC_8") (pintype "bidirectional"))
      (node (ref "U7") (pin "1") (pinfunction "VDD_1") (pintype "power_in"))
      (node (ref "U7") (pin "2") (pinfunction "PS_2") (pintype "input"))
      (node (ref "U8") (pin "1") (pinfunction "VBAT_1") (pintype "power_in"))
      (node (ref "U8") (pin "24") (pinfunction "VDD_1_24") (pintype "power_in"))
      (node (ref "U8") (pin "36") (pinfunction "VDD_2_36") (pintype "power_in"))
      (node (ref "U8") (pin "48") (pinfunction "VDD_3_48") (pintype "power_in"))
      (node (ref "X1") (pin "4") (pinfunction "S_4") (pintype "passive"))
    )
    (net (code "2") (name "BT0") (class "Default")
      (node (ref "R1") (pin "2") (pinfunction "2_2") (pintype "passive"))
      (node (ref "U8") (pin "44") (pinfunction "BOOT0_44") (pintype "input"))
    )
    (net (code "3") (name "BUZZER") (class "Default")
      (node (ref "BUZ") (pin "1") (pinfunction "1_1") (pintype "passive"))
      (node (ref "U8") (pin "18") (pinfunction "PB0_18") (pintype "bidirectional"))
    )
    (net (code "4") (name "CMISO") (class "Default")
      (node (ref "J4") (pin "1") (pinfunction "1_1") (pintype "bidirectional"))
      (node (ref "U4") (pin "5") (pinfunction "MISO_5") (pintype "bidirectional"))
      (node (ref "U6") (pin "2") (pinfunction "SO(D1)_2") (pintype "bidirectional"))
    )
    (net (code "5") (name "CMOSI") (class "Default")
      (node (ref "J4") (pin "4") (pinfunction "4_4") (pintype "bidirectional"))
      (node (ref "U4") (pin "4") (pinfunction "MOSI_4") (pintype "bidirectional"))
      (node (ref "U6") (pin "5") (pinfunction "SI(D0)_5") (pintype "bidirectional"))
    )
    (net (code "6") (name "CS") (class "Default")
      (node (ref "J1") (pin "2") (pinfunction "CD/DAT3(~{CS})_2") (pintype "bidirectional"))
      (node (ref "U8") (pin "29") (pinfunction "PA8_29") (pintype "bidirectional"))
    )
    (net (code "7") (name "CSCK") (class "Default")
      (node (ref "J4") (pin "3") (pinfunction "3_3") (pintype "bidirectional"))
      (node (ref "U4") (pin "3") (pinfunction "SCK_3") (pintype "output"))
      (node (ref "U6") (pin "6") (pinfunction "SCK_6") (pintype "bidirectional"))
    )
    (net (code "8") (name "CSF") (class "Default")
      (node (ref "IC1") (pin "1") (pinfunction "R_1") (pintype "open_collector"))
      (node (ref "U8") (pin "25") (pinfunction "PB12_25") (pintype "bidirectional"))
    )
    (net (code "9") (name "CSN_EE") (class "Default")
      (node (ref "J4") (pin "5") (pinfunction "5_5") (pintype "bidirectional"))
      (node (ref "U4") (pin "6") (pinfunction "CSN_6") (pintype "output"))
      (node (ref "U6") (pin "1") (pinfunction "~{CS}_1") (pintype "bidirectional"))
    )
    (net (code "10") (name "DRDY") (class "Default")
      (node (ref "J2") (pin "1") (pinfunction "1_1") (pintype "passive"))
      (node (ref "U8") (pin "2") (pinfunction "PC13_2") (pintype "bidirectional"))
    )
    (net (code "11") (name "GND") (class "Default")
      (node (ref "C1") (pin "2") (pinfunction "2_2") (pintype "passive"))
      (node (ref "C11") (pin "1") (pinfunction "1_1") (pintype "passive"))
      (node (ref "C12") (pin "1") (pinfunction "1_1") (pintype "passive"))
      (node (ref "C14") (pin "1") (pinfunction "1_1") (pintype "passive"))
      (node (ref "C15") (pin "1") (pinfunction "1_1") (pintype "passive"))
      (node (ref "C16") (pin "1") (pinfunction "1_1") (pintype "passive"))
      (node (ref "C17") (pin "1") (pinfunction "1_1") (pintype "passive"))
      (node (ref "C2") (pin "2") (pinfunction "2_2") (pintype "passive"))
      (node (ref "C3") (pin "2") (pinfunction "2_2") (pintype "passive"))
      (node (ref "C4") (pin "1") (pinfunction "1_1") (pintype "passive"))
      (node (ref "C5") (pin "1") (pinfunction "1_1") (pintype "passive"))
      (node (ref "C6") (pin "2") (pinfunction "2_2") (pintype "passive"))
      (node (ref "C7") (pin "2") (pinfunction "2_2") (pintype "passive"))
      (node (ref "C8") (pin "2") (pinfunction "2_2") (pintype "passive"))
      (node (ref "C9") (pin "2") (pinfunction "2_2") (pintype "passive"))
      (node (ref "IC1") (pin "4") (pinfunction "GND_4") (pintype "power_in"))
      (node (ref "J1") (pin "6") (pinfunction "VSS_6") (pintype "bidirectional"))
      (node (ref "J2") (pin "4") (pinfunction "4_4") (pintype "passive"))
      (node (ref "J3") (pin "4") (pinfunction "4_4") (pintype "passive"))
      (node (ref "J4") (pin "6") (pinfunction "6_6") (pintype "bidirectional"))
      (node (ref "J5") (pin "GND1") (pinfunction "GND_GND1") (pintype "power_in"))
      (node (ref "J5") (pin "SHLD1") (pinfunction "SHIELD_SHLD1") (pintype "bidirectional"))
      (node (ref "J5") (pin "SHLD2") (pinfunction "SHIELD_SHLD2") (pintype "bidirectional"))
      (node (ref "J5") (pin "SHLD3") (pinfunction "SHIELD_SHLD3") (pintype "bidirectional"))
      (node (ref "LPS-1") (pin "3") (pinfunction "RES_3") (pintype "bidirectional"))
      (node (ref "LPS-1") (pin "5") (pinfunction "SDO/SAO_5") (pintype "bidirectional"))
      (node (ref "LPS-1") (pin "8") (pinfunction "GND_8") (pintype "bidirectional"))
      (node (ref "LPS-1") (pin "9") (pinfunction "GND_9") (pintype "bidirectional"))
      (node (ref "LPSC1") (pin "2") (pinfunction "2_2") (pintype "passive"))
      (node (ref "LPSC2") (pin "2") (pinfunction "2_2") (pintype "passive"))
      (node (ref "LS1") (pin "N") (pinfunction "N_N") (pintype "passive"))
      (node (ref "MS5611") (pin "2") (pinfunction "2_2") (pintype "passive"))
      (node (ref "OSCC1") (pin "2") (pinfunction "2_2") (pintype "passive"))
      (node (ref "OSCC2") (pin "2") (pinfunction "2_2") (pintype "passive"))
      (node (ref "POWER1") (pin "1") (pinfunction "1_1") (pintype "passive"))
      (node (ref "R1") (pin "1") (pinfunction "1_1") (pintype "passive"))
      (node (ref "RC1") (pin "C") (pinfunction "-_C") (pintype "passive"))
      (node (ref "RC2") (pin "2") (pinfunction "2_2") (pintype "passive"))
      (node (ref "RC3") (pin "2") (pinfunction "2_2") (pintype "passive"))
      (node (ref "RC4") (pin "C") (pinfunction "-_C") (pintype "passive"))
      (node (ref "RRO") (pin "2") (pinfunction "2_2") (pintype "passive"))
      (node (ref "RRO1") (pin "2") (pinfunction "2_2") (pintype "passive"))
      (node (ref "SL1") (pin "1") (pinfunction "1_1") (pintype "passive"))
      (node (ref "U1") (pin "16") (pinfunction "GND_16") (pintype "power_in"))
      (node (ref "U2") (pin "16") (pinfunction "GND_16") (pintype "power_in"))
      (node (ref "U3") (pin "1") (pinfunction "GND_1") (pintype "power_in"))
      (node (ref "U3") (pin "5") (pinfunction "SDO_5") (pintype "bidirectional"))
      (node (ref "U3") (pin "7") (pinfunction "GND_7") (pintype "power_in"))
      (node (ref "U4") (pin "16") (pinfunction "GND_16") (pintype "power_in"))
      (node (ref "U4") (pin "8") (pinfunction "I2C_ENB_8") (pintype "input"))
      (node (ref "U5") (pin "1") (pinfunction "ADJ_1") (pintype "power_in"))
      (node (ref "U6") (pin "4") (pinfunction "GND_4") (pintype "bidirectional"))
      (node (ref "U7") (pin "3") (pinfunction "GND_3") (pintype "passive"))
      (node (ref "U7") (pin "4") (pinfunction "CSB_2_4") (pintype "input"))
      (node (ref "U7") (pin "5") (pinfunction "CSB_5") (pintype "input"))
      (node (ref "U8") (pin "23") (pinfunction "VSS_1_23") (pintype "power_in"))
      (node (ref "U8") (pin "35") (pinfunction "VSS_2_35") (pintype "power_in"))
      (node (ref "U8") (pin "47") (pinfunction "VSS_3_47") (pintype "power_in"))
      (node (ref "U8") (pin "8") (pinfunction "VSSA_8") (pintype "power_in"))
      (node (ref "VDDA1") (pin "2") (pinfunction "2_2") (pintype "passive"))
      (node (ref "VDDA2") (pin "2") (pinfunction "2_2") (pintype "passive"))
      (node (ref "WPR") (pin "1") (pinfunction "1_1") (pintype "passive"))
      (node (ref "X1") (pin "1") (pinfunction "S_1") (pintype "passive"))
      (node (ref "Y2") (pin "2") (pinfunction "GND_2") (pintype "passive"))
      (node (ref "Y2") (pin "4") (pinfunction "GND_4") (pintype "passive"))
    )
    (net (code "12") (name "HOLD") (class "Default")
      (node (ref "HOLDR") (pin "1") (pinfunction "1_1") (pintype "passive"))
      (node (ref "IC1") (pin "7") (pinfunction "SET_7") (pintype "input"))
      (node (ref "U8") (pin "31") (pinfunction "PA10_31") (pintype "bidirectional"))
    )
    (net (code "13") (name "HT") (class "Default")
      (node (ref "U5") (pin "4") (pinfunction "HT_4") (pintype "bidirectional"))
    )
    (net (code "14") (name "INT") (class "Default")
      (node (ref "U4") (pin "13") (pinfunction "INT_13") (pintype "output"))
      (node (ref "U8") (pin "39") (pinfunction "PB3_39") (pintype "bidirectional"))
    )
    (net (code "15") (name "INT1") (class "Default")
      (node (ref "LPS-1") (pin "7") (pinfunction "INT1_7") (pintype "bidirectional"))
      (node (ref "U8") (pin "40") (pinfunction "PB4_40") (pintype "bidirectional"))
    )
    (net (code "16") (name "LED") (class "Default")
      (node (ref "RD1") (pin "A") (pinfunction "A_A") (pintype "passive"))
      (node (ref "U8") (pin "17") (pinfunction "PA7_17") (pintype "bidirectional"))
    )
    (net (code "17") (name "MISO") (class "Default")
      (node (ref "IC1") (pin "2") (pinfunction "G_2") (pintype "open_collector"))
      (node (ref "J1") (pin "7") (pinfunction "DAT0(DO)_7") (pintype "bidirectional"))
      (node (ref "U8") (pin "27") (pinfunction "PB14_27") (pintype "bidirectional"))
    )
    (net (code "18") (name "MOSI") (class "Default")
      (node (ref "IC1") (pin "5") (pinfunction "DO_5") (pintype "output"))
      (node (ref "J1") (pin "3") (pinfunction "CMD(DI)_3") (pintype "bidirectional"))
      (node (ref "U8") (pin "28") (pinfunction "PB15_28") (pintype "bidirectional"))
    )
    (net (code "19") (name "NRST") (class "Default")
      (node (ref "C17") (pin "2") (pinfunction "2_2") (pintype "passive"))
      (node (ref "R2") (pin "1") (pinfunction "1_1") (pintype "passive"))
      (node (ref "U8") (pin "7") (pinfunction "NRST_7") (pintype "bidirectional"))
    )
    (net (code "20") (name "Net-(BUZ-Pad2)") (class "Default")
      (node (ref "BUZ") (pin "2") (pinfunction "2_2") (pintype "passive"))
      (node (ref "LS1") (pin "P") (pinfunction "P_P") (pintype "passive"))
    )
    (net (code "21") (name "Net-(POWER1-Pad2)") (class "Default")
      (node (ref "POWER1") (pin "2") (pinfunction "2_2") (pintype "passive"))
      (node (ref "SW1") (pin "1") (pinfunction "1_1") (pintype "passive"))
    )
    (net (code "22") (name "Net-(RC1-+)") (class "Default")
      (node (ref "RC1") (pin "A") (pinfunction "+_A") (pintype "passive"))
      (node (ref "RC2") (pin "1") (pinfunction "1_1") (pintype "passive"))
      (node (ref "RGD") (pin "C") (pinfunction "C_C") (pintype "passive"))
      (node (ref "U5") (pin "3") (pinfunction "VIN_3") (pintype "input"))
    )
    (net (code "23") (name "Net-(RC4-+)") (class "Default")
      (node (ref "F") (pin "1") (pinfunction "1_1") (pintype "bidirectional"))
      (node (ref "RC3") (pin "1") (pinfunction "1_1") (pintype "passive"))
      (node (ref "RC4") (pin "A") (pinfunction "+_A") (pintype "passive"))
      (node (ref "U5") (pin "2") (pinfunction "VOUT_2") (pintype "output"))
    )
    (net (code "24") (name "Net-(RD-PadC)") (class "Default")
      (node (ref "RD") (pin "C") (pinfunction "C_C") (pintype "passive"))
      (node (ref "RRO") (pin "1") (pinfunction "1_1") (pintype "passive"))
    )
    (net (code "25") (name "Net-(RD1-PadC)") (class "Default")
      (node (ref "RD1") (pin "C") (pinfunction "C_C") (pintype "passive"))
      (node (ref "RRO1") (pin "1") (pinfunction "1_1") (pintype "passive"))
    )
    (net (code "26") (name "Net-(U1-I2C_ENB)") (class "Default")
      (node (ref "R3") (pin "2") (pinfunction "2_2") (pintype "passive"))
      (node (ref "U1") (pin "8") (pinfunction "I2C_ENB_8") (pintype "input"))
    )
    (net (code "27") (name "Net-(U1-LED_IND)") (class "Default")
      (node (ref "D2") (pin "C") (pinfunction "C_C") (pintype "passive"))
      (node (ref "U1") (pin "18") (pinfunction "LED_IND_18") (pintype "output"))
    )
    (net (code "28") (name "Net-(U2-I2C_ENB)") (class "Default")
      (node (ref "R5") (pin "2") (pinfunction "2_2") (pintype "passive"))
      (node (ref "U2") (pin "8") (pinfunction "I2C_ENB_8") (pintype "input"))
    )
    (net (code "29") (name "Net-(U2-LED_IND)") (class "Default")
      (node (ref "D3") (pin "C") (pinfunction "C_C") (pintype "passive"))
      (node (ref "U2") (pin "18") (pinfunction "LED_IND_18") (pintype "output"))
    )
    (net (code "30") (name "Net-(U4-LED_IND)") (class "Default")
      (node (ref "D1") (pin "C") (pinfunction "C_C") (pintype "passive"))
      (node (ref "U4") (pin "18") (pinfunction "LED_IND_18") (pintype "output"))
    )
    (net (code "31") (name "OSC_IN") (class "Default")
      (node (ref "OSCC1") (pin "1") (pinfunction "1_1") (pintype "passive"))
      (node (ref "U8") (pin "5") (pinfunction "OSC_IN_5") (pintype "input"))
      (node (ref "Y2") (pin "1") (pinfunction "1_1") (pintype "passive"))
    )
    (net (code "32") (name "OSC_OUT") (class "Default")
      (node (ref "OSCC2") (pin "1") (pinfunction "1_1") (pintype "passive"))
      (node (ref "U8") (pin "6") (pinfunction "OSC_OUT_6") (pintype "output"))
      (node (ref "Y2") (pin "3") (pinfunction "3_3") (pintype "passive"))
    )
    (net (code "33") (name "RESN") (class "Default")
      (node (ref "R7") (pin "1") (pinfunction "1_1") (pintype "passive"))
      (node (ref "SL1") (pin "2") (pinfunction "2_2") (pintype "passive"))
      (node (ref "U4") (pin "2") (pinfunction "RESN_2") (pintype "input"))
    )
    (net (code "34") (name "RX1") (class "Default")
      (node (ref "U4") (pin "12") (pinfunction "TX/SDA_S_12") (pintype "bidirectional"))
      (node (ref "U8") (pin "43") (pinfunction "PB7_43") (pintype "bidirectional"))
    )
    (net (code "35") (name "RX2") (class "Default")
      (node (ref "U8") (pin "13") (pinfunction "PA3_13") (pintype "bidirectional"))
      (node (ref "X1") (pin "3") (pinfunction "S_3") (pintype "passive"))
    )
    (net (code "36") (name "SCK") (class "Default")
      (node (ref "IC1") (pin "6") (pinfunction "DIN_6") (pintype "input"))
      (node (ref "J1") (pin "5") (pinfunction "CLK(SCK)_5") (pintype "bidirectional"))
      (node (ref "U8") (pin "26") (pinfunction "PB13_26") (pintype "bidirectional"))
    )
    (net (code "37") (name "SCL") (class "Default")
      (node (ref "J2") (pin "3") (pinfunction "3_3") (pintype "passive"))
      (node (ref "LPS-1") (pin "2") (pinfunction "SCL/SPC_2") (pintype "bidirectional"))
      (node (ref "R4") (pin "1") (pinfunction "1_1") (pintype "passive"))
      (node (ref "U3") (pin "4") (pinfunction "SCK_4") (pintype "input"))
      (node (ref "U7") (pin "8") (pinfunction "SCLK_8") (pintype "input"))
      (node (ref "U8") (pin "45") (pinfunction "PB8_45") (pintype "bidirectional"))
    )
    (net (code "38") (name "SCL_M") (class "Default")
      (node (ref "R15") (pin "1") (pinfunction "1_1") (pintype "passive"))
      (node (ref "U1") (pin "9") (pinfunction "SCL_M_9") (pintype "output"))
      (node (ref "U2") (pin "9") (pinfunction "SCL_M_9") (pintype "output"))
      (node (ref "U4") (pin "9") (pinfunction "SCL_M_9") (pintype "output"))
    )
    (net (code "39") (name "SDA") (class "Default")
      (node (ref "J2") (pin "2") (pinfunction "2_2") (pintype "passive"))
      (node (ref "LPS-1") (pin "4") (pinfunction "SDA/SDI/SDO_4") (pintype "bidirectional"))
      (node (ref "R6") (pin "1") (pinfunction "1_1") (pintype "passive"))
      (node (ref "U3") (pin "3") (pinfunction "SDI_3") (pintype "bidirectional"))
      (node (ref "U7") (pin "7") (pinfunction "SDI/SDA_7") (pintype "bidirectional"))
      (node (ref "U8") (pin "46") (pinfunction "PB9_46") (pintype "bidirectional"))
    )
    (net (code "40") (name "SDA_M") (class "Default")
      (node (ref "R16") (pin "1") (pinfunction "1_1") (pintype "passive"))
      (node (ref "U1") (pin "10") (pinfunction "SDA_M_10") (pintype "bidirectional"))
      (node (ref "U2") (pin "10") (pinfunction "SDA_M_10") (pintype "bidirectional"))
      (node (ref "U4") (pin "10") (pinfunction "SDA_M_10") (pintype "bidirectional"))
    )
    (net (code "41") (name "SLV1_R") (class "Default")
      (node (ref "R14") (pin "1") (pinfunction "1_1") (pintype "passive"))
      (node (ref "U1") (pin "2") (pinfunction "RESN_2") (pintype "input"))
      (node (ref "U4") (pin "1") (pinfunction "SLV1_RESN_1") (pintype "bidirectional"))
    )
    (net (code "42") (name "SLV2_R") (class "Default")
      (node (ref "R10") (pin "1") (pinfunction "1_1") (pintype "passive"))
      (node (ref "U2") (pin "2") (pinfunction "RESN_2") (pintype "input"))
      (node (ref "U4") (pin "20") (pinfunction "SLV2_RESN_20") (pintype "output"))
    )
    (net (code "43") (name "SWCLK") (class "Default")
      (node (ref "J3") (pin "3") (pinfunction "3_3") (pintype "passive"))
      (node (ref "U8") (pin "37") (pinfunction "PA14_37") (pintype "bidirectional"))
    )
    (net (code "44") (name "SWDIO") (class "Default")
      (node (ref "J3") (pin "2") (pinfunction "2_2") (pintype "passive"))
      (node (ref "U8") (pin "34") (pinfunction "PA13_34") (pintype "bidirectional"))
    )
    (net (code "45") (name "TX1") (class "Default")
      (node (ref "U4") (pin "11") (pinfunction "RX/SCL_S_11") (pintype "bidirectional"))
      (node (ref "U8") (pin "42") (pinfunction "PB6_42") (pintype "bidirectional"))
    )
    (net (code "46") (name "TX2") (class "Default")
      (node (ref "U8") (pin "12") (pinfunction "PA2_12") (pintype "bidirectional"))
      (node (ref "X1") (pin "2") (pinfunction "S_2") (pintype "passive"))
    )
    (net (code "47") (name "USB_N") (class "Default")
      (node (ref "J5") (pin "D-1") (pinfunction "D-_D-1") (pintype "bidirectional"))
      (node (ref "U8") (pin "32") (pinfunction "PA11_32") (pintype "bidirectional"))
    )
    (net (code "48") (name "USB_P") (class "Default")
      (node (ref "J5") (pin "D+1") (pinfunction "D+_D+1") (pintype "bidirectional"))
      (node (ref "U8") (pin "33") (pinfunction "PA12_33") (pintype "bidirectional"))
    )
    (net (code "49") (name "VDDA") (class "Default")
      (node (ref "L2") (pin "2") (pinfunction "2_2") (pintype "passive"))
      (node (ref "U8") (pin "9") (pinfunction "VDDA_9") (pintype "power_in"))
      (node (ref "VDDA1") (pin "1") (pinfunction "1_1") (pintype "passive"))
      (node (ref "VDDA2") (pin "1") (pinfunction "1_1") (pintype "passive"))
    )
    (net (code "50") (name "VIN") (class "Default")
      (node (ref "J5") (pin "VBUS1") (pinfunction "VBUS_VBUS1") (pintype "power_in"))
      (node (ref "RGD") (pin "A") (pinfunction "A_A") (pintype "passive"))
      (node (ref "SW1") (pin "2") (pinfunction "2_2") (pintype "passive"))
    )
    (net (code "51") (name "WP") (class "Default")
      (node (ref "IC1") (pin "3") (pinfunction "B_3") (pintype "open_collector"))
      (node (ref "U8") (pin "30") (pinfunction "PA9_30") (pintype "bidirectional"))
      (node (ref "WPR") (pin "2") (pinfunction "2_2") (pintype "passive"))
    )
    (net (code "52") (name "unconnected-(J1B-DAT1(RSV)-Pad8)") (class "Default")
      (node (ref "J1") (pin "8") (pinfunction "DAT1(RSV)_8") (pintype "bidirectional"))
    )
    (net (code "53") (name "unconnected-(J1B-DAT2(NC)-Pad1)") (class "Default")
      (node (ref "J1") (pin "1") (pinfunction "DAT2(NC)_1") (pintype "bidirectional"))
    )
    (net (code "54") (name "unconnected-(J5-USBID-PadID1)") (class "Default")
      (node (ref "J5") (pin "ID1") (pinfunction "USBID_ID1") (pintype "bidirectional"))
    )
    (net (code "55") (name "unconnected-(U1-CSN-Pad6)") (class "Default")
      (node (ref "U1") (pin "6") (pinfunction "CSN_6") (pintype "output"))
    )
    (net (code "56") (name "unconnected-(U1-INT-Pad13)") (class "Default")
      (node (ref "U1") (pin "13") (pinfunction "INT_13") (pintype "output"))
    )
    (net (code "57") (name "unconnected-(U1-LED_DRV-Pad15)") (class "Default")
      (node (ref "U1") (pin "15") (pinfunction "LED_DRV_15") (pintype "output"))
    )
    (net (code "58") (name "unconnected-(U1-MISO-Pad5)") (class "Default")
      (node (ref "U1") (pin "5") (pinfunction "MISO_5") (pintype "bidirectional"))
    )
    (net (code "59") (name "unconnected-(U1-MOSI-Pad4)") (class "Default")
      (node (ref "U1") (pin "4") (pinfunction "MOSI_4") (pintype "bidirectional"))
    )
    (net (code "60") (name "unconnected-(U1-RX{slash}SCL_S-Pad11)") (class "Default")
      (node (ref "U1") (pin "11") (pinfunction "RX/SCL_S_11") (pintype "bidirectional"))
    )
    (net (code "61") (name "unconnected-(U1-SCK-Pad3)") (class "Default")
      (node (ref "U1") (pin "3") (pinfunction "SCK_3") (pintype "output"))
    )
    (net (code "62") (name "unconnected-(U1-SLV1_RESN-Pad1)") (class "Default")
      (node (ref "U1") (pin "1") (pinfunction "SLV1_RESN_1") (pintype "bidirectional"))
    )
    (net (code "63") (name "unconnected-(U1-SLV2_RESN-Pad20)") (class "Default")
      (node (ref "U1") (pin "20") (pinfunction "SLV2_RESN_20") (pintype "output"))
    )
    (net (code "64") (name "unconnected-(U1-TX{slash}SDA_S-Pad12)") (class "Default")
      (node (ref "U1") (pin "12") (pinfunction "TX/SDA_S_12") (pintype "bidirectional"))
    )
    (net (code "65") (name "unconnected-(U2-CSN-Pad6)") (class "Default")
      (node (ref "U2") (pin "6") (pinfunction "CSN_6") (pintype "output"))
    )
    (net (code "66") (name "unconnected-(U2-INT-Pad13)") (class "Default")
      (node (ref "U2") (pin "13") (pinfunction "INT_13") (pintype "output"))
    )
    (net (code "67") (name "unconnected-(U2-LED_DRV-Pad15)") (class "Default")
      (node (ref "U2") (pin "15") (pinfunction "LED_DRV_15") (pintype "output"))
    )
    (net (code "68") (name "unconnected-(U2-MISO-Pad5)") (class "Default")
      (node (ref "U2") (pin "5") (pinfunction "MISO_5") (pintype "bidirectional"))
    )
    (net (code "69") (name "unconnected-(U2-MOSI-Pad4)") (class "Default")
      (node (ref "U2") (pin "4") (pinfunction "MOSI_4") (pintype "bidirectional"))
    )
    (net (code "70") (name "unconnected-(U2-RX{slash}SCL_S-Pad11)") (class "Default")
      (node (ref "U2") (pin "11") (pinfunction "RX/SCL_S_11") (pintype "bidirectional"))
    )
    (net (code "71") (name "unconnected-(U2-SCK-Pad3)") (class "Default")
      (node (ref "U2") (pin "3") (pinfunction "SCK_3") (pintype "output"))
    )
    (net (code "72") (name "unconnected-(U2-SLV1_RESN-Pad1)") (class "Default")
      (node (ref "U2") (pin "1") (pinfunction "SLV1_RESN_1") (pintype "bidirectional"))
    )
    (net (code "73") (name "unconnected-(U2-SLV2_RESN-Pad20)") (class "Default")
      (node (ref "U2") (pin "20") (pinfunction "SLV2_RESN_20") (pintype "output"))
    )
    (net (code "74") (name "unconnected-(U2-TX{slash}SDA_S-Pad12)") (class "Default")
      (node (ref "U2") (pin "12") (pinfunction "TX/SDA_S_12") (pintype "bidirectional"))
    )
    (net (code "75") (name "unconnected-(U4-LED_DRV-Pad15)") (class "Default")
      (node (ref "U4") (pin "15") (pinfunction "LED_DRV_15") (pintype "output"))
    )
    (net (code "76") (name "unconnected-(U7-SDO-Pad6)") (class "Default")
      (node (ref "U7") (pin "6") (pinfunction "SDO_6") (pintype "output"))
    )
    (net (code "77") (name "unconnected-(U8A-PA0-WKUP-Pad10)") (class "Default")
      (node (ref "U8") (pin "10") (pinfunction "PA0-WKUP_10") (pintype "bidirectional"))
    )
    (net (code "78") (name "unconnected-(U8A-PA1-Pad11)") (class "Default")
      (node (ref "U8") (pin "11") (pinfunction "PA1_11") (pintype "bidirectional"))
    )
    (net (code "79") (name "unconnected-(U8A-PA4-Pad14)") (class "Default")
      (node (ref "U8") (pin "14") (pinfunction "PA4_14") (pintype "bidirectional"))
    )
    (net (code "80") (name "unconnected-(U8A-PA5-Pad15)") (class "Default")
      (node (ref "U8") (pin "15") (pinfunction "PA5_15") (pintype "bidirectional"))
    )
    (net (code "81") (name "unconnected-(U8A-PA6-Pad16)") (class "Default")
      (node (ref "U8") (pin "16") (pinfunction "PA6_16") (pintype "bidirectional"))
    )
    (net (code "82") (name "unconnected-(U8A-PA15-Pad38)") (class "Default")
      (node (ref "U8") (pin "38") (pinfunction "PA15_38") (pintype "bidirectional"))
    )
    (net (code "83") (name "unconnected-(U8A-PB1-Pad19)") (class "Default")
      (node (ref "U8") (pin "19") (pinfunction "PB1_19") (pintype "bidirectional"))
    )
    (net (code "84") (name "unconnected-(U8A-PB2-Pad20)") (class "Default")
      (node (ref "U8") (pin "20") (pinfunction "PB2_20") (pintype "bidirectional"))
    )
    (net (code "85") (name "unconnected-(U8A-PB5-Pad41)") (class "Default")
      (node (ref "U8") (pin "41") (pinfunction "PB5_41") (pintype "bidirectional"))
    )
    (net (code "86") (name "unconnected-(U8A-PB10-Pad21)") (class "Default")
      (node (ref "U8") (pin "21") (pinfunction "PB10_21") (pintype "bidirectional"))
    )
    (net (code "87") (name "unconnected-(U8A-PB11-Pad22)") (class "Default")
      (node (ref "U8") (pin "22") (pinfunction "PB11_22") (pintype "bidirectional"))
    )
    (net (code "88") (name "unconnected-(U8A-PC14-OSC32_IN-Pad3)") (class "Default")
      (node (ref "U8") (pin "3") (pinfunction "PC14-OSC32_IN_3") (pintype "bidirectional"))
    )
    (net (code "89") (name "unconnected-(U8A-PC15-OSC32_OUT-Pad4)") (class "Default")
      (node (ref "U8") (pin "4") (pinfunction "PC15-OSC32_OUT_4") (pintype "bidirectional"))
    )
  )
)
